# reflex_brainboard_RevG.net
KiCad netlist of a schematic drawn in Altium Designer
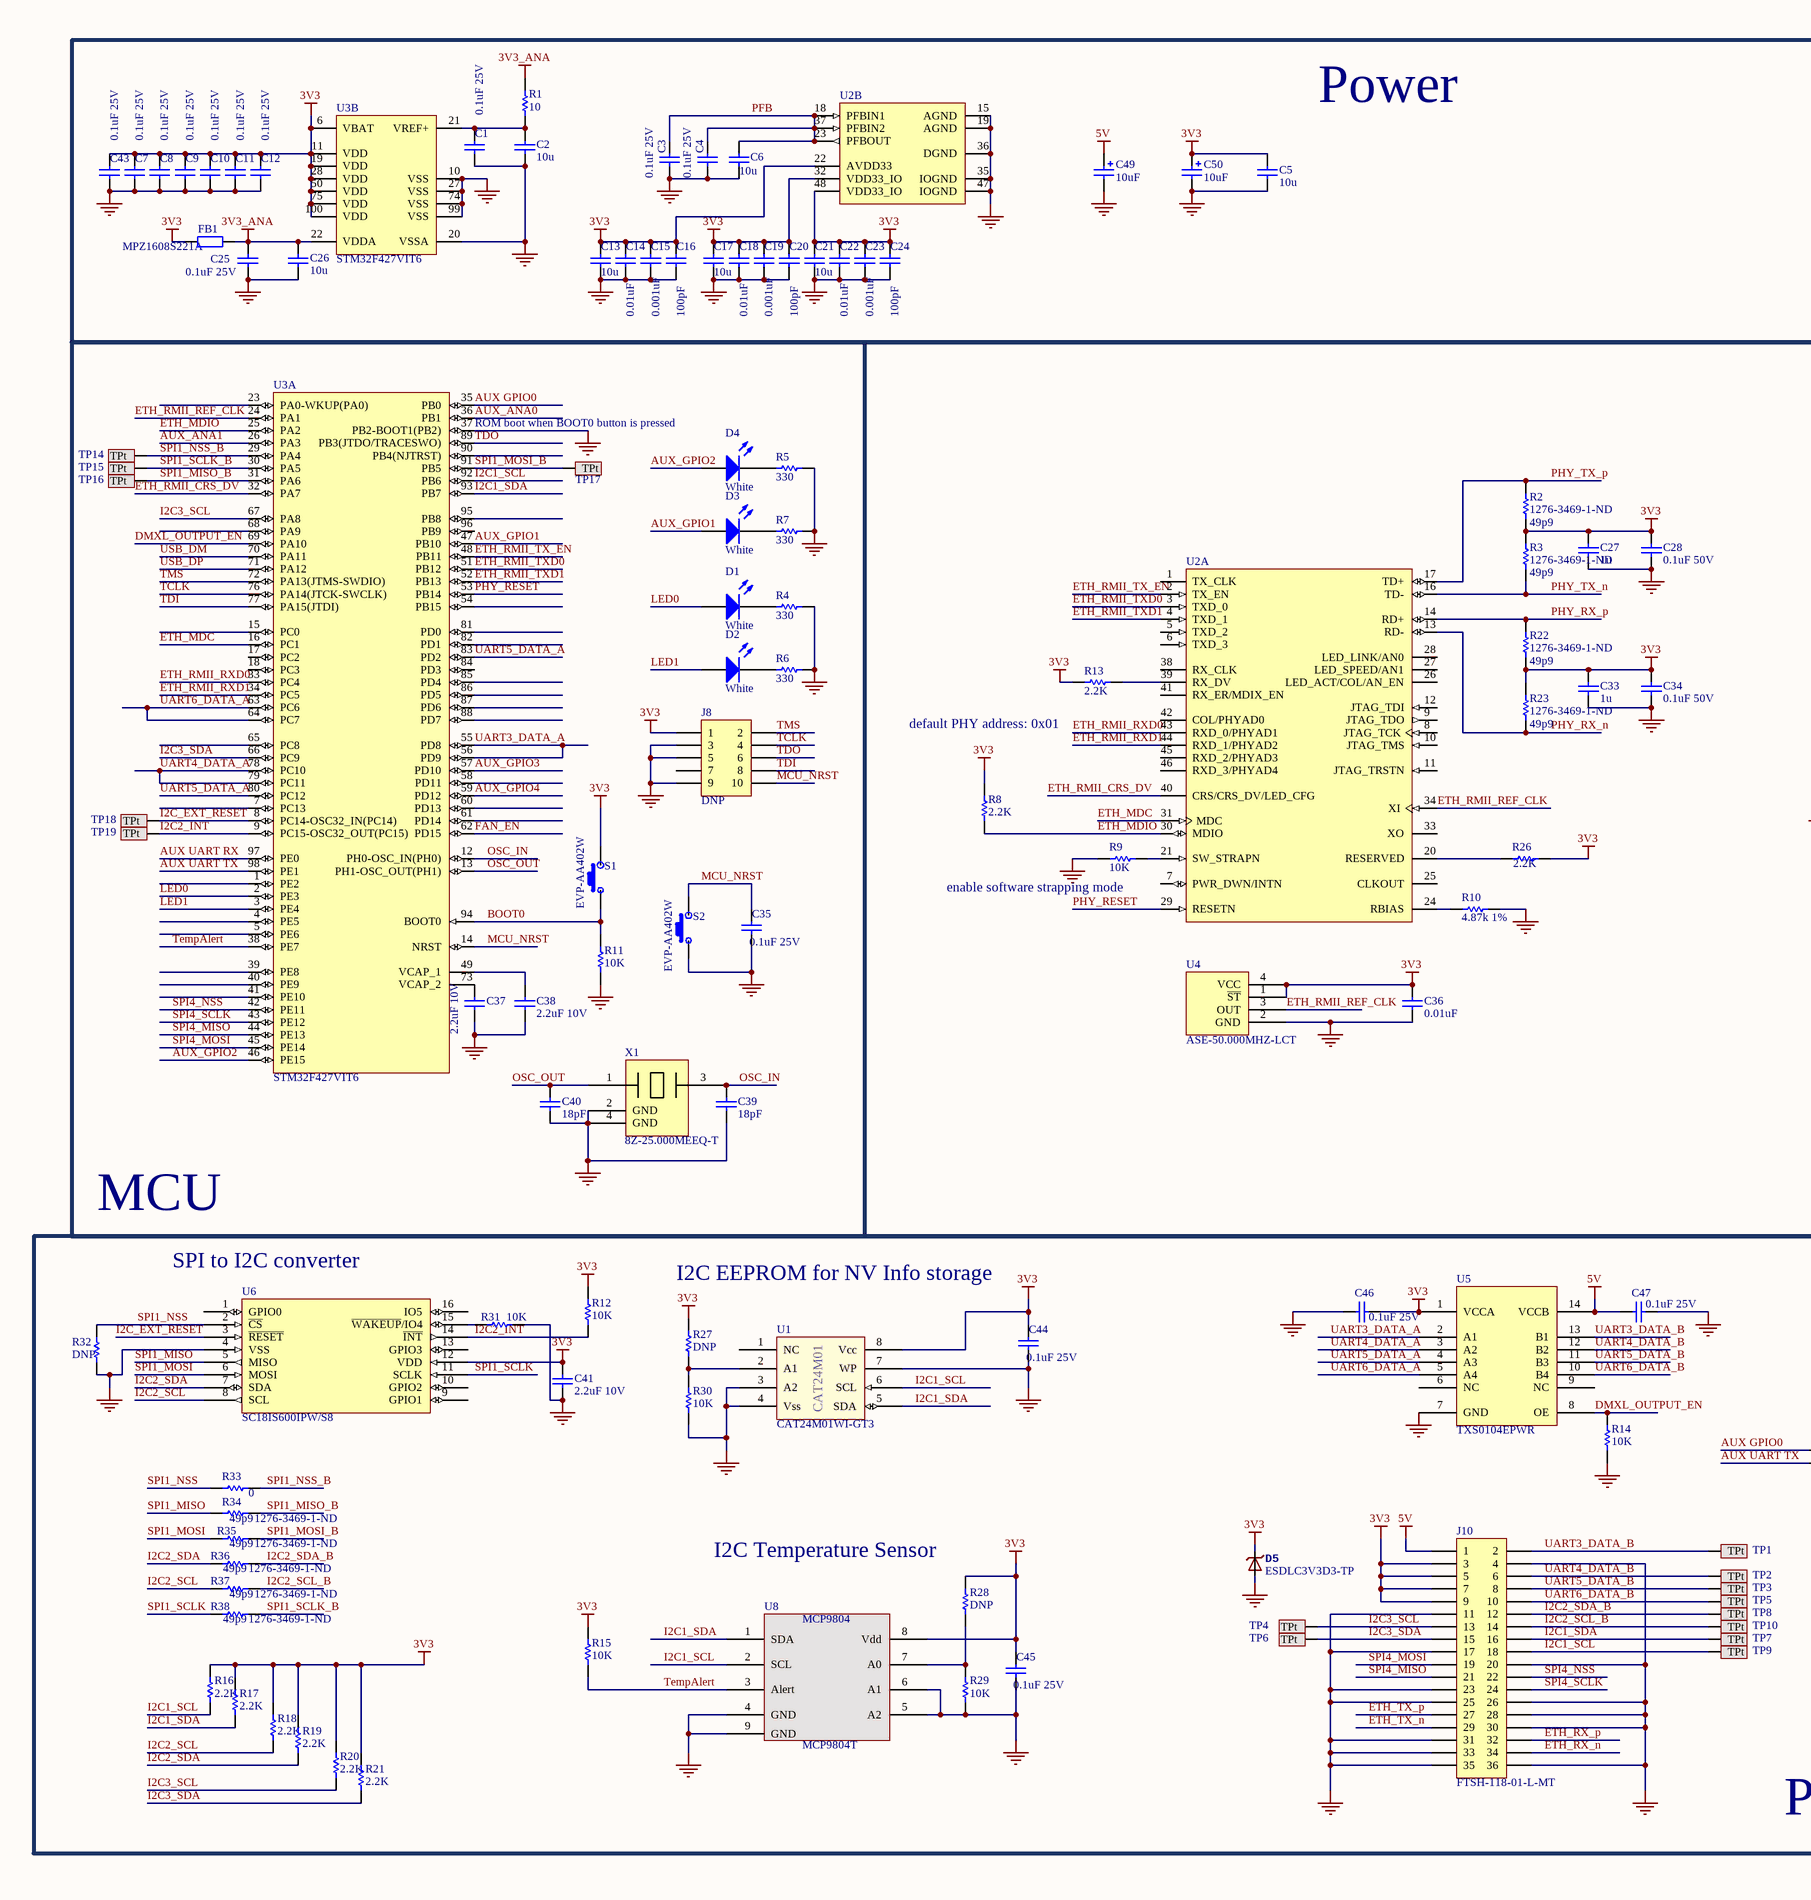
[diagram p0: reflex_brainboard_RevG.SchDoc, left]
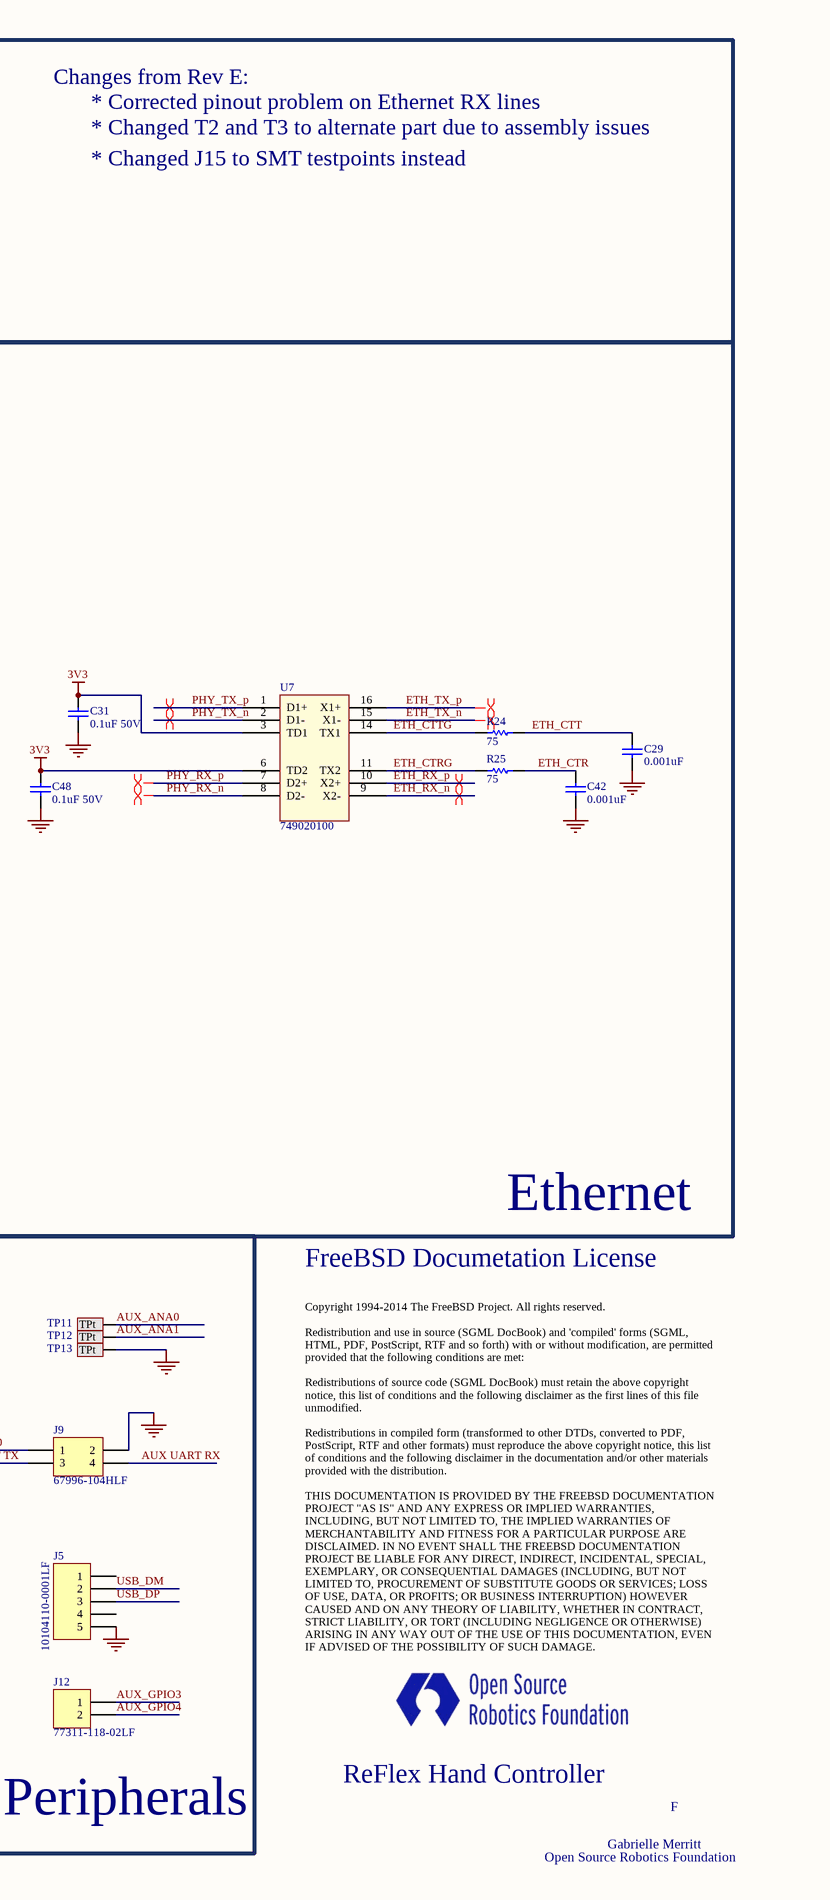
[diagram p1: reflex_brainboard_RevG.SchDoc, right]

(export (version "E")
  (design (tool "Eeschema 10.0.6"))
  (components
    (comp (ref "C1")
      (value "0.1uF 25V")
      (footprint "Generic_0603")
      (description "Capacitor 0.1uF 0603 package")
      (libsource (lib "RHR") (part "Cap_0603_0.1uF_25V"))
    )
    (comp (ref "C2")
      (value "10u")
      (footprint "GENERIC_0603")
      (description "Capacitor")
      (fields
        (field (name "MANUFACTURER") "TDK Corporation")
        (field (name "MANUFACTURER PART NUMBER") "C1608X5R1E106M080AC")
      )
      (libsource (lib "RHR") (part "Cap_0603_10uF"))
    )
    (comp (ref "C3")
      (value "0.1uF 25V")
      (footprint "Generic_0603")
      (description "Capacitor 0.1uF 0603 package")
      (libsource (lib "RHR") (part "Cap_0603_0.1uF_25V"))
    )
    (comp (ref "C4")
      (value "0.1uF 25V")
      (footprint "Generic_0603")
      (description "Capacitor 0.1uF 0603 package")
      (libsource (lib "RHR") (part "Cap_0603_0.1uF_25V"))
    )
    (comp (ref "C5")
      (value "10u")
      (footprint "GENERIC_0603")
      (description "Capacitor")
      (fields
        (field (name "MANUFACTURER") "TDK Corporation")
        (field (name "MANUFACTURER PART NUMBER") "C1608X5R1E106M080AC")
      )
      (libsource (lib "RHR") (part "Cap_0603_10uF"))
    )
    (comp (ref "C6")
      (value "10u")
      (footprint "GENERIC_0603")
      (description "Capacitor")
      (fields
        (field (name "MANUFACTURER") "TDK Corporation")
        (field (name "MANUFACTURER PART NUMBER") "C1608X5R1E106M080AC")
      )
      (libsource (lib "RHR") (part "Cap_0603_10uF"))
    )
    (comp (ref "C7")
      (value "0.1uF 25V")
      (footprint "Generic_0603")
      (description "Capacitor 0.1uF 0603 package")
      (libsource (lib "RHR") (part "Cap_0603_0.1uF_25V"))
    )
    (comp (ref "C8")
      (value "0.1uF 25V")
      (footprint "Generic_0603")
      (description "Capacitor 0.1uF 0603 package")
      (libsource (lib "RHR") (part "Cap_0603_0.1uF_25V"))
    )
    (comp (ref "C9")
      (value "0.1uF 25V")
      (footprint "Generic_0603")
      (description "Capacitor 0.1uF 0603 package")
      (libsource (lib "RHR") (part "Cap_0603_0.1uF_25V"))
    )
    (comp (ref "C10")
      (value "0.1uF 25V")
      (footprint "Generic_0603")
      (description "Capacitor 0.1uF 0603 package")
      (libsource (lib "RHR") (part "Cap_0603_0.1uF_25V"))
    )
    (comp (ref "C11")
      (value "0.1uF 25V")
      (footprint "Generic_0603")
      (description "Capacitor 0.1uF 0603 package")
      (libsource (lib "RHR") (part "Cap_0603_0.1uF_25V"))
    )
    (comp (ref "C12")
      (value "0.1uF 25V")
      (footprint "Generic_0603")
      (description "Capacitor 0.1uF 0603 package")
      (libsource (lib "RHR") (part "Cap_0603_0.1uF_25V"))
    )
    (comp (ref "C13")
      (value "10u")
      (footprint "GENERIC_0603")
      (description "Capacitor")
      (fields
        (field (name "MANUFACTURER") "TDK Corporation")
        (field (name "MANUFACTURER PART NUMBER") "C1608X5R1E106M080AC")
      )
      (libsource (lib "RHR") (part "Cap_0603_10uF"))
    )
    (comp (ref "C14")
      (value "0.01uF")
      (footprint "Generic_0402")
      (description "Capacitor 0.01uF 0402 package")
      (libsource (lib "RHR") (part "Cap_0402_0p01uF"))
    )
    (comp (ref "C15")
      (value "0.001uF")
      (footprint "Generic_0402")
      (description "Capacitor 0.001uF 0402 package")
      (libsource (lib "RHR") (part "Cap_0402_0p001uF"))
    )
    (comp (ref "C16")
      (value "100pF")
      (footprint "Generic_0402")
      (description "Capacitor 100pF 0402 package")
      (libsource (lib "RHR") (part "Cap_0402_100pF"))
    )
    (comp (ref "C17")
      (value "10u")
      (footprint "GENERIC_0603")
      (description "Capacitor")
      (fields
        (field (name "MANUFACTURER") "TDK Corporation")
        (field (name "MANUFACTURER PART NUMBER") "C1608X5R1E106M080AC")
      )
      (libsource (lib "RHR") (part "Cap_0603_10uF"))
    )
    (comp (ref "C18")
      (value "0.01uF")
      (footprint "Generic_0402")
      (description "Capacitor 0.01uF 0402 package")
      (libsource (lib "RHR") (part "Cap_0402_0p01uF"))
    )
    (comp (ref "C19")
      (value "0.001uF")
      (footprint "Generic_0402")
      (description "Capacitor 0.001uF 0402 package")
      (libsource (lib "RHR") (part "Cap_0402_0p001uF"))
    )
    (comp (ref "C20")
      (value "100pF")
      (footprint "Generic_0402")
      (description "Capacitor 100pF 0402 package")
      (libsource (lib "RHR") (part "Cap_0402_100pF"))
    )
    (comp (ref "C21")
      (value "10u")
      (footprint "GENERIC_0603")
      (description "Capacitor")
      (fields
        (field (name "MANUFACTURER") "TDK Corporation")
        (field (name "MANUFACTURER PART NUMBER") "C1608X5R1E106M080AC")
      )
      (libsource (lib "RHR") (part "Cap_0603_10uF"))
    )
    (comp (ref "C22")
      (value "0.01uF")
      (footprint "Generic_0402")
      (description "Capacitor 0.01uF 0402 package")
      (libsource (lib "RHR") (part "Cap_0402_0p01uF"))
    )
    (comp (ref "C23")
      (value "0.001uF")
      (footprint "Generic_0402")
      (description "Capacitor 0.001uF 0402 package")
      (libsource (lib "RHR") (part "Cap_0402_0p001uF"))
    )
    (comp (ref "C24")
      (value "100pF")
      (footprint "Generic_0402")
      (description "Capacitor 100pF 0402 package")
      (libsource (lib "RHR") (part "Cap_0402_100pF"))
    )
    (comp (ref "C25")
      (value "0.1uF 25V")
      (footprint "Generic_0603")
      (description "Capacitor 0.1uF 0603 package")
      (libsource (lib "RHR") (part "Cap_0603_0.1uF_25V"))
    )
    (comp (ref "C26")
      (value "10u")
      (footprint "GENERIC_0603")
      (description "Capacitor")
      (fields
        (field (name "MANUFACTURER") "TDK Corporation")
        (field (name "MANUFACTURER PART NUMBER") "C1608X5R1E106M080AC")
      )
      (libsource (lib "RHR") (part "Cap_0603_10uF"))
    )
    (comp (ref "C27")
      (value "1u")
      (footprint "Generic_0402")
      (description "Capacitor")
      (libsource (lib "RHR") (part "Cap_0402_1uF"))
    )
    (comp (ref "C28")
      (value "0.1uF 50V")
      (footprint "Generic_0402")
      (description "Capacitor 0.1uF 0402 package")
      (fields (field (name "Comment") "0.1uF"))
      (libsource (lib "RHR") (part "Cap_0402_0p1uF_50V"))
    )
    (comp (ref "C29")
      (value "0.001uF")
      (footprint "Generic_0402")
      (description "Capacitor 0.001uF 0402 package")
      (libsource (lib "RHR") (part "Cap_0402_0p001uF"))
    )
    (comp (ref "C31")
      (value "0.1uF 50V")
      (footprint "Generic_0402")
      (description "Capacitor 0.1uF 0402 package")
      (fields (field (name "Comment") "0.1uF"))
      (libsource (lib "RHR") (part "Cap_0402_0p1uF_50V"))
    )
    (comp (ref "C33")
      (value "1u")
      (footprint "Generic_0402")
      (description "Capacitor")
      (libsource (lib "RHR") (part "Cap_0402_1uF"))
    )
    (comp (ref "C34")
      (value "0.1uF 50V")
      (footprint "Generic_0402")
      (description "Capacitor 0.1uF 0402 package")
      (fields (field (name "Comment") "0.1uF"))
      (libsource (lib "RHR") (part "Cap_0402_0p1uF_50V"))
    )
    (comp (ref "C35")
      (value "0.1uF 25V")
      (footprint "Generic_0603")
      (description "Capacitor 0.1uF 0603 package")
      (libsource (lib "RHR") (part "Cap_0603_0.1uF_25V"))
    )
    (comp (ref "C36")
      (value "0.01uF")
      (footprint "Generic_0402")
      (description "Capacitor 0.01uF 0402 package")
      (libsource (lib "RHR") (part "Cap_0402_0p01uF"))
    )
    (comp (ref "C37")
      (value "2.2uF 10V")
      (footprint "Generic_0603")
      (description "Capacitor 2.2uF 0603 package")
      (libsource (lib "RHR") (part "Cap_0603_2p2uF_10V"))
    )
    (comp (ref "C38")
      (value "2.2uF 10V")
      (footprint "Generic_0603")
      (description "Capacitor 2.2uF 0603 package")
      (libsource (lib "RHR") (part "Cap_0603_2p2uF_10V"))
    )
    (comp (ref "C39")
      (value "18pF")
      (footprint "Generic_0402")
      (description "Capacitor 18pF 0402 package")
      (libsource (lib "RHR") (part "Cap_0402_18pF"))
    )
    (comp (ref "C40")
      (value "18pF")
      (footprint "Generic_0402")
      (description "Capacitor 18pF 0402 package")
      (libsource (lib "RHR") (part "Cap_0402_18pF"))
    )
    (comp (ref "C41")
      (value "2.2uF 10V")
      (footprint "Generic_0603")
      (description "Capacitor 2.2uF 0603 package")
      (libsource (lib "RHR") (part "Cap_0603_2p2uF_10V"))
    )
    (comp (ref "C42")
      (value "0.001uF")
      (footprint "Generic_0402")
      (description "Capacitor 0.001uF 0402 package")
      (libsource (lib "RHR") (part "Cap_0402_0p001uF"))
    )
    (comp (ref "C43")
      (value "0.1uF 25V")
      (footprint "Generic_0603")
      (description "Capacitor 0.1uF 0603 package")
      (libsource (lib "RHR") (part "Cap_0603_0.1uF_25V"))
    )
    (comp (ref "C44")
      (value "0.1uF 25V")
      (footprint "Generic_0603")
      (description "Capacitor 0.1uF 0603 package")
      (libsource (lib "RHR") (part "Cap_0603_0.1uF_25V"))
    )
    (comp (ref "C45")
      (value "0.1uF 25V")
      (footprint "Generic_0603")
      (description "Capacitor 0.1uF 0603 package")
      (libsource (lib "RHR") (part "Cap_0603_0.1uF_25V"))
    )
    (comp (ref "C46")
      (value "0.1uF 25V")
      (footprint "Generic_0603")
      (description "Capacitor 0.1uF 0603 package")
      (libsource (lib "RHR") (part "Cap_0603_0.1uF_25V"))
    )
    (comp (ref "C47")
      (value "0.1uF 25V")
      (footprint "Generic_0603")
      (description "Capacitor 0.1uF 0603 package")
      (libsource (lib "RHR") (part "Cap_0603_0.1uF_25V"))
    )
    (comp (ref "C48")
      (value "0.1uF 50V")
      (footprint "Generic_0402")
      (description "Capacitor 0.1uF 0402 package")
      (fields (field (name "Comment") "0.1uF"))
      (libsource (lib "RHR") (part "Cap_0402_0p1uF_50V"))
    )
    (comp (ref "C49")
      (value "10uF")
      (footprint "GENERIC_0805P")
      (description "Polarized Capacitor (Radial)")
      (libsource (lib "RHR") (part "Cap 0805P_10uF"))
    )
    (comp (ref "C50")
      (value "10uF")
      (footprint "GENERIC_0805P")
      (description "Polarized Capacitor (Radial)")
      (libsource (lib "RHR") (part "Cap 0805P_10uF"))
    )
    (comp (ref "D1")
      (value "White")
      (footprint "0402_LED_WHITE")
      (description "Surface mount LEDs")
      (fields (field (name "Comment") "LED White"))
      (libsource (lib "RHR") (part "LED_White_0402"))
    )
    (comp (ref "D2")
      (value "White")
      (footprint "0402_LED_WHITE")
      (description "Surface mount LEDs")
      (fields (field (name "Comment") "LED White"))
      (libsource (lib "RHR") (part "LED_White_0402"))
    )
    (comp (ref "D3")
      (value "White")
      (footprint "0402_LED_WHITE")
      (description "Surface mount LEDs")
      (fields (field (name "Comment") "LED White"))
      (libsource (lib "RHR") (part "LED_White_0402"))
    )
    (comp (ref "D4")
      (value "White")
      (footprint "0402_LED_WHITE")
      (description "Surface mount LEDs")
      (fields (field (name "Comment") "LED White"))
      (libsource (lib "RHR") (part "LED_White_0402"))
    )
    (comp (ref "D5")
      (value "ESDLC3V3D3-TP")
      (footprint "SOD-323")
      (fields (field (name "MANUFACTURER") "Micro Commercial Co"))
      (libsource (lib "RHR") (part "Diode_ESDLC3V3D3-TP"))
    )
    (comp (ref "FB1")
      (value "MPZ1608S221A")
      (footprint "GENERIC_0603")
      (description "Ferrite Bead")
      (fields (field (name "MANUFACTURER") "TDK Corporation"))
      (libsource (lib "RHR") (part "FerriteBead"))
    )
    (comp (ref "J5")
      (value "10104110-0001LF")
      (footprint "FCI-10104110")
      (description "USB Micro Connector")
      (libsource (lib "RHR") (part "Conn_USB_Micro"))
    )
    (comp (ref "J8")
      (value "DNP")
      (footprint "CNCTECH_3220-10-0300-00")
      (description "Header, 5-Pin, Dual row")
      (libsource (lib "RHR") (part "Header 5X2"))
    )
    (comp (ref "J9")
      (value "67996-104HLF")
      (footprint "HDR2X2")
      (description "Header, 2-Pin, Dual row")
      (libsource (lib "RHR") (part "Header 2X2"))
    )
    (comp (ref "J10")
      (value "FTSH-118-01-L-MT")
      (footprint "FTSH-118-01-L-MT")
      (description "Header, 18-Pin, Dual row, Hybrid SMT/Thru")
      (libsource (lib "RHR") (part "Header 18X2 RA MT"))
    )
    (comp (ref "J12")
      (value "77311-118-02LF")
      (footprint "HDR1X2")
      (description "Header, 2-Pin")
      (libsource (lib "RHR") (part "Header 2"))
    )
    (comp (ref "R1")
      (value "10")
      (footprint "Generic_0402")
      (description "Resistor  10 ohm")
      (libsource (lib "RHR") (part "Res_0402_10_1pct"))
    )
    (comp (ref "R2")
      (value "49p9")
      (footprint "Generic_0402")
      (description "Resistor 49.9 ohm")
      (fields
        (field (name "SUPPLIER PART NUMBER 1") "1276-3469-1-ND")
        (field (name "Comment") "Res_0402_49p9_1pct")
      )
      (libsource (lib "RHR") (part "Res_0402_49p9_1pct"))
    )
    (comp (ref "R3")
      (value "49p9")
      (footprint "Generic_0402")
      (description "Resistor 49.9 ohm")
      (fields
        (field (name "SUPPLIER PART NUMBER 1") "1276-3469-1-ND")
        (field (name "Comment") "Res_0402_49p9_1pct")
      )
      (libsource (lib "RHR") (part "Res_0402_49p9_1pct"))
    )
    (comp (ref "R4")
      (value "330")
      (footprint "Generic_0402")
      (description "RES 330 OHM 1/10W 1% 0402 SMD")
      (libsource (lib "RHR") (part "Res_0402_330"))
    )
    (comp (ref "R5")
      (value "330")
      (footprint "Generic_0402")
      (description "RES 330 OHM 1/10W 1% 0402 SMD")
      (libsource (lib "RHR") (part "Res_0402_330"))
    )
    (comp (ref "R6")
      (value "330")
      (footprint "Generic_0402")
      (description "RES 330 OHM 1/10W 1% 0402 SMD")
      (libsource (lib "RHR") (part "Res_0402_330"))
    )
    (comp (ref "R7")
      (value "330")
      (footprint "Generic_0402")
      (description "RES 330 OHM 1/10W 1% 0402 SMD")
      (libsource (lib "RHR") (part "Res_0402_330"))
    )
    (comp (ref "R8")
      (value "2.2K")
      (footprint "Generic_0402")
      (description "Resistor 2.2 Kohm")
      (fields (field (name "Comment") "Res_0402_2.2K"))
      (libsource (lib "RHR") (part "Res_0402_2.2K"))
    )
    (comp (ref "R9")
      (value "10K")
      (footprint "Generic_0402")
      (description "Resistor 10 Kohm")
      (fields (field (name "Comment") "Res_0402_10K_1pct"))
      (libsource (lib "RHR") (part "Res_0402_10K_1pct"))
    )
    (comp (ref "R10")
      (value "4.87k 1%")
      (footprint "Generic_0402")
      (description "75R 0.063W 5% 0402 (1005 Metric)  SMD")
      (libsource (lib "RHR") (part "Res_0402_4p87K_1pct"))
    )
    (comp (ref "R11")
      (value "10K")
      (footprint "Generic_0402")
      (description "Resistor 10 Kohm")
      (fields (field (name "Comment") "Res_0402_10K_1pct"))
      (libsource (lib "RHR") (part "Res_0402_10K_1pct"))
    )
    (comp (ref "R12")
      (value "10K")
      (footprint "Generic_0402")
      (description "Resistor 10 Kohm")
      (fields (field (name "Comment") "Res_0402_10K_1pct"))
      (libsource (lib "RHR") (part "Res_0402_10K_1pct"))
    )
    (comp (ref "R13")
      (value "2.2K")
      (footprint "Generic_0402")
      (description "Resistor 2.2 Kohm")
      (fields (field (name "Comment") "Res_0402_2.2K"))
      (libsource (lib "RHR") (part "Res_0402_2.2K"))
    )
    (comp (ref "R14")
      (value "10K")
      (footprint "Generic_0402")
      (description "Resistor 10 Kohm")
      (fields (field (name "Comment") "Res_0402_10K_1pct"))
      (libsource (lib "RHR") (part "Res_0402_10K_1pct"))
    )
    (comp (ref "R15")
      (value "10K")
      (footprint "Generic_0402")
      (description "Resistor 10 Kohm")
      (fields (field (name "Comment") "Res_0402_10K_1pct"))
      (libsource (lib "RHR") (part "Res_0402_10K_1pct"))
    )
    (comp (ref "R16")
      (value "2.2K")
      (footprint "Generic_0402")
      (description "Resistor 2.2 Kohm")
      (fields (field (name "Comment") "Res_0402_2.2K"))
      (libsource (lib "RHR") (part "Res_0402_2.2K"))
    )
    (comp (ref "R17")
      (value "2.2K")
      (footprint "Generic_0402")
      (description "Resistor 2.2 Kohm")
      (fields (field (name "Comment") "Res_0402_2.2K"))
      (libsource (lib "RHR") (part "Res_0402_2.2K"))
    )
    (comp (ref "R18")
      (value "2.2K")
      (footprint "Generic_0402")
      (description "Resistor 2.2 Kohm")
      (fields (field (name "Comment") "Res_0402_2.2K"))
      (libsource (lib "RHR") (part "Res_0402_2.2K"))
    )
    (comp (ref "R19")
      (value "2.2K")
      (footprint "Generic_0402")
      (description "Resistor 2.2 Kohm")
      (fields (field (name "Comment") "Res_0402_2.2K"))
      (libsource (lib "RHR") (part "Res_0402_2.2K"))
    )
    (comp (ref "R20")
      (value "2.2K")
      (footprint "Generic_0402")
      (description "Resistor 2.2 Kohm")
      (fields (field (name "Comment") "Res_0402_2.2K"))
      (libsource (lib "RHR") (part "Res_0402_2.2K"))
    )
    (comp (ref "R21")
      (value "2.2K")
      (footprint "Generic_0402")
      (description "Resistor 2.2 Kohm")
      (fields (field (name "Comment") "Res_0402_2.2K"))
      (libsource (lib "RHR") (part "Res_0402_2.2K"))
    )
    (comp (ref "R22")
      (value "49p9")
      (footprint "Generic_0402")
      (description "Resistor 49.9 ohm")
      (fields
        (field (name "SUPPLIER PART NUMBER 1") "1276-3469-1-ND")
        (field (name "Comment") "Res_0402_49p9_1pct")
      )
      (libsource (lib "RHR") (part "Res_0402_49p9_1pct"))
    )
    (comp (ref "R23")
      (value "49p9")
      (footprint "Generic_0402")
      (description "Resistor 49.9 ohm")
      (fields
        (field (name "SUPPLIER PART NUMBER 1") "1276-3469-1-ND")
        (field (name "Comment") "Res_0402_49p9_1pct")
      )
      (libsource (lib "RHR") (part "Res_0402_49p9_1pct"))
    )
    (comp (ref "R24")
      (value "75")
      (footprint "Generic_0402")
      (description "75R 0.063W 5% 0402 (1005 Metric)  SMD")
      (libsource (lib "RHR") (part "Res_0402_75_1pct"))
    )
    (comp (ref "R25")
      (value "75")
      (footprint "Generic_0402")
      (description "75R 0.063W 5% 0402 (1005 Metric)  SMD")
      (libsource (lib "RHR") (part "Res_0402_75_1pct"))
    )
    (comp (ref "R26")
      (value "2.2K")
      (footprint "Generic_0402")
      (description "Resistor 2.2 Kohm")
      (fields (field (name "Comment") "Res_0402_2.2K"))
      (libsource (lib "RHR") (part "Res_0402_2.2K"))
    )
    (comp (ref "R27")
      (value "DNP")
      (footprint "Generic_0402")
      (description "Resistor 0402 DNP")
      (fields (field (name "Comment") "Res_0402_DNP"))
      (libsource (lib "RHR") (part "Res_0402_DNP"))
    )
    (comp (ref "R28")
      (value "DNP")
      (footprint "Generic_0402")
      (description "Resistor 0402 DNP")
      (fields (field (name "Comment") "Res_0402_DNP"))
      (libsource (lib "RHR") (part "Res_0402_DNP"))
    )
    (comp (ref "R29")
      (value "10K")
      (footprint "Generic_0402")
      (description "Resistor 10 Kohm")
      (fields (field (name "Comment") "Res_0402_10K_1pct"))
      (libsource (lib "RHR") (part "Res_0402_10K_1pct"))
    )
    (comp (ref "R30")
      (value "10K")
      (footprint "Generic_0402")
      (description "Resistor 10 Kohm")
      (fields (field (name "Comment") "Res_0402_10K_1pct"))
      (libsource (lib "RHR") (part "Res_0402_10K_1pct"))
    )
    (comp (ref "R31")
      (value "10K")
      (footprint "Generic_0402")
      (description "Resistor 10 Kohm")
      (fields (field (name "Comment") "Res_0402_10K_1pct"))
      (libsource (lib "RHR") (part "Res_0402_10K_1pct"))
    )
    (comp (ref "R32")
      (value "DNP")
      (footprint "Generic_0402")
      (description "Resistor 0402 DNP")
      (fields (field (name "Comment") "Res_0402_DNP"))
      (libsource (lib "RHR") (part "Res_0402_DNP"))
    )
    (comp (ref "R33")
      (value "0")
      (footprint "GENERIC_0402")
      (description "RES SMD 0 OHM JUMPER 1/10W 0402")
      (fields (field (name "Comment") "Res_0402_0"))
      (libsource (lib "RHR") (part "Res_0402_0"))
    )
    (comp (ref "R34")
      (value "49p9")
      (footprint "Generic_0402")
      (description "Resistor 49.9 ohm")
      (fields
        (field (name "SUPPLIER PART NUMBER 1") "1276-3469-1-ND")
        (field (name "Comment") "Res_0402_49p9_1pct")
      )
      (libsource (lib "RHR") (part "Res_0402_49p9_1pct"))
    )
    (comp (ref "R35")
      (value "49p9")
      (footprint "Generic_0402")
      (description "Resistor 49.9 ohm")
      (fields
        (field (name "SUPPLIER PART NUMBER 1") "1276-3469-1-ND")
        (field (name "Comment") "Res_0402_49p9_1pct")
      )
      (libsource (lib "RHR") (part "Res_0402_49p9_1pct"))
    )
    (comp (ref "R36")
      (value "49p9")
      (footprint "Generic_0402")
      (description "Resistor 49.9 ohm")
      (fields
        (field (name "SUPPLIER PART NUMBER 1") "1276-3469-1-ND")
        (field (name "Comment") "Res_0402_49p9_1pct")
      )
      (libsource (lib "RHR") (part "Res_0402_49p9_1pct"))
    )
    (comp (ref "R37")
      (value "49p9")
      (footprint "Generic_0402")
      (description "Resistor 49.9 ohm")
      (fields
        (field (name "SUPPLIER PART NUMBER 1") "1276-3469-1-ND")
        (field (name "Comment") "Res_0402_49p9_1pct")
      )
      (libsource (lib "RHR") (part "Res_0402_49p9_1pct"))
    )
    (comp (ref "R38")
      (value "49p9")
      (footprint "Generic_0402")
      (description "Resistor 49.9 ohm")
      (fields
        (field (name "SUPPLIER PART NUMBER 1") "1276-3469-1-ND")
        (field (name "Comment") "Res_0402_49p9_1pct")
      )
      (libsource (lib "RHR") (part "Res_0402_49p9_1pct"))
    )
    (comp (ref "S1")
      (value "EVP-AA402W")
      (footprint "EVPAA402_switch")
      (description "Momentary Push button, NO")
      (libsource (lib "RHR") (part "Pushbutton_EVP-AA402W"))
    )
    (comp (ref "S2")
      (value "EVP-AA402W")
      (footprint "EVPAA402_switch")
      (description "Momentary Push button, NO")
      (libsource (lib "RHR") (part "Pushbutton_EVP-AA402W"))
    )
    (comp (ref "TP1")
      (value "SMT Pad")
      (footprint "TP_PAD_20mil")
      (description "SMT pad for test")
      (libsource (lib "RHR") (part "TP_SMT_20mil"))
    )
    (comp (ref "TP2")
      (value "SMT Pad")
      (footprint "TP_PAD_20mil")
      (description "SMT pad for test")
      (libsource (lib "RHR") (part "TP_SMT_20mil"))
    )
    (comp (ref "TP3")
      (value "SMT Pad")
      (footprint "TP_PAD_20mil")
      (description "SMT pad for test")
      (libsource (lib "RHR") (part "TP_SMT_20mil"))
    )
    (comp (ref "TP4")
      (value "SMT Pad")
      (footprint "TP_PAD_20mil")
      (description "SMT pad for test")
      (libsource (lib "") (part "TP_SMT_20mil_1"))
    )
    (comp (ref "TP5")
      (value "SMT Pad")
      (footprint "TP_PAD_20mil")
      (description "SMT pad for test")
      (libsource (lib "RHR") (part "TP_SMT_20mil"))
    )
    (comp (ref "TP6")
      (value "SMT Pad")
      (footprint "TP_PAD_20mil")
      (description "SMT pad for test")
      (libsource (lib "") (part "TP_SMT_20mil_1"))
    )
    (comp (ref "TP7")
      (value "SMT Pad")
      (footprint "TP_PAD_20mil")
      (description "SMT pad for test")
      (libsource (lib "RHR") (part "TP_SMT_20mil"))
    )
    (comp (ref "TP8")
      (value "SMT Pad")
      (footprint "TP_PAD_20mil")
      (description "SMT pad for test")
      (libsource (lib "RHR") (part "TP_SMT_20mil"))
    )
    (comp (ref "TP9")
      (value "SMT Pad")
      (footprint "TP_PAD_20mil")
      (description "SMT pad for test")
      (libsource (lib "RHR") (part "TP_SMT_20mil"))
    )
    (comp (ref "TP10")
      (value "SMT Pad")
      (footprint "TP_PAD_20mil")
      (description "SMT pad for test")
      (libsource (lib "RHR") (part "TP_SMT_20mil"))
    )
    (comp (ref "TP11")
      (value "SMT Pad")
      (footprint "TP_PAD_20mil")
      (description "SMT pad for test")
      (libsource (lib "") (part "TP_SMT_20mil_1"))
    )
    (comp (ref "TP12")
      (value "SMT Pad")
      (footprint "TP_PAD_20mil")
      (description "SMT pad for test")
      (libsource (lib "") (part "TP_SMT_20mil_1"))
    )
    (comp (ref "TP13")
      (value "SMT Pad")
      (footprint "TP_PAD_20mil")
      (description "SMT pad for test")
      (libsource (lib "") (part "TP_SMT_20mil_1"))
    )
    (comp (ref "TP14")
      (value "SMT Pad")
      (footprint "TP_PAD_20mil")
      (description "SMT pad for test")
      (libsource (lib "") (part "TP_SMT_20mil_1"))
    )
    (comp (ref "TP15")
      (value "SMT Pad")
      (footprint "TP_PAD_20mil")
      (description "SMT pad for test")
      (libsource (lib "") (part "TP_SMT_20mil_1"))
    )
    (comp (ref "TP16")
      (value "SMT Pad")
      (footprint "TP_PAD_20mil")
      (description "SMT pad for test")
      (libsource (lib "") (part "TP_SMT_20mil_1"))
    )
    (comp (ref "TP17")
      (value "SMT Pad")
      (footprint "TP_PAD_20mil")
      (description "SMT pad for test")
      (libsource (lib "RHR") (part "TP_SMT_20mil"))
    )
    (comp (ref "TP18")
      (value "SMT Pad")
      (footprint "TP_PAD_20mil")
      (description "SMT pad for test")
      (libsource (lib "") (part "TP_SMT_20mil_1"))
    )
    (comp (ref "TP19")
      (value "SMT Pad")
      (footprint "TP_PAD_20mil")
      (description "SMT pad for test")
      (libsource (lib "") (part "TP_SMT_20mil_1"))
    )
    (comp (ref "U1")
      (value "CAT24M01WI-GT3")
      (footprint "SOIC8")
      (description "I2C EEPROM 1Mbit")
      (libsource (lib "RHR") (part "IC_EEPROM_I2C_1Mbit"))
    )
    (comp (ref "U2")
      (value "TLK110PT")
      (footprint "PT0048A_M")
      (libsource (lib "Altium Content Vault") (part "TI-TLK110-LQFP_PT-48"))
    )
    (comp (ref "U3")
      (value "STM32F427VIT6")
      (footprint "STM-LQFP100_N")
      (fields (field (name "MANUFACTURER") "STMicroelectronics"))
      (libsource (lib "RHR") (part "MC-ARM-STM32F4X7-SQ100"))
    )
    (comp (ref "U4")
      (value "ASE-50.000MHZ-LCT")
      (footprint "OSCILLATOR_3.2x2.5")
      (libsource (lib "RHR") (part "oscillator_3.2x2.5"))
    )
    (comp (ref "U5")
      (value "TXS0104EPWR")
      (footprint "TXS0104EPWR")
      (description "Level Shifter")
      (libsource (lib "RHR") (part "IC_LevelShifter_TXS0104EPWR"))
    )
    (comp (ref "U6")
      (value "SC18IS600IPW/S8")
      (footprint "SOT403-1-TSSOP16")
      (description "SPI to I2C-bus interface")
      (libsource (lib "Schlib1") (part "SC18IS600IPW/S8"))
    )
    (comp (ref "U7")
      (value "749020100")
      (footprint "Wurth749020100")
      (description "Ethernet Magnetics Wurth 749020100")
      (libsource (lib "RHR") (part "IC_EthernetMagnetics"))
    )
    (comp (ref "U8")
      (value "MCP9804T")
      (footprint "Temp_MCP9804T")
      (description "I2C Temp Sensor MCP9804T-E/MC")
      (libsource (lib "RHR") (part "IC_Temp_Sensor_MCP9804_I2C"))
    )
    (comp (ref "X1")
      (value "8Z-25.000MEEQ-T")
      (footprint "CRYSTAL_2_2.5")
      (libsource (lib "RHR") (part "CRYSTAL"))
    )
  )
  (nets
    (net (code "1") (name "/AUX GPIO0") (class "Default")
      (node (ref "J9") (pin "1") (pinfunction "1_1") (pintype "passive"))
      (node (ref "U3") (pin "35") (pinfunction "PB0_35") (pintype "bidirectional"))
    )
    (net (code "2") (name "/AUX UART RX") (class "Default")
      (node (ref "J9") (pin "4") (pinfunction "4_4") (pintype "passive"))
      (node (ref "U3") (pin "97") (pinfunction "PE0_97") (pintype "bidirectional"))
    )
    (net (code "3") (name "/AUX UART TX") (class "Default")
      (node (ref "J9") (pin "3") (pinfunction "3_3") (pintype "passive"))
      (node (ref "U3") (pin "98") (pinfunction "PE1_98") (pintype "bidirectional"))
    )
    (net (code "4") (name "/AUX_ANA0") (class "Default")
      (node (ref "TP11") (pin "1") (pinfunction "TPt_1") (pintype "passive"))
      (node (ref "U3") (pin "36") (pinfunction "PB1_36") (pintype "bidirectional"))
    )
    (net (code "5") (name "/AUX_ANA1") (class "Default")
      (node (ref "TP12") (pin "1") (pinfunction "TPt_1") (pintype "passive"))
      (node (ref "U3") (pin "26") (pinfunction "PA3_26") (pintype "bidirectional"))
    )
    (net (code "6") (name "/AUX_GPIO1") (class "Default")
      (node (ref "D3") (pin "1") (pinfunction "A_1") (pintype "passive"))
      (node (ref "U3") (pin "47") (pinfunction "PB10_47") (pintype "bidirectional"))
    )
    (net (code "7") (name "/AUX_GPIO2") (class "Default")
      (node (ref "D4") (pin "1") (pinfunction "A_1") (pintype "passive"))
      (node (ref "U3") (pin "46") (pinfunction "PE15_46") (pintype "bidirectional"))
    )
    (net (code "8") (name "/AUX_GPIO3") (class "Default")
      (node (ref "J12") (pin "1") (pinfunction "1_1") (pintype "passive"))
      (node (ref "U3") (pin "57") (pinfunction "PD10_57") (pintype "bidirectional"))
    )
    (net (code "9") (name "/AUX_GPIO4") (class "Default")
      (node (ref "J12") (pin "2") (pinfunction "2_2") (pintype "passive"))
      (node (ref "U3") (pin "59") (pinfunction "PD12_59") (pintype "bidirectional"))
    )
    (net (code "10") (name "/BOOT0") (class "Default")
      (node (ref "R11") (pin "2") (pinfunction "2_2") (pintype "passive"))
      (node (ref "S1") (pin "2") (pinfunction "2_2") (pintype "power_in"))
      (node (ref "U3") (pin "94") (pinfunction "BOOT0_94") (pintype "input"))
    )
    (net (code "11") (name "/DMXL_OUTPUT_EN") (class "Default")
      (node (ref "R14") (pin "2") (pinfunction "2_2") (pintype "passive"))
      (node (ref "U3") (pin "69") (pinfunction "PA10_69") (pintype "bidirectional"))
      (node (ref "U5") (pin "8") (pinfunction "OE_8") (pintype "power_in"))
    )
    (net (code "12") (name "/ETH_CTR") (class "Default")
      (node (ref "C42") (pin "2") (pinfunction "2_2") (pintype "passive"))
      (node (ref "R25") (pin "2") (pinfunction "2_2") (pintype "passive"))
    )
    (net (code "13") (name "/ETH_CTRG") (class "Default")
      (node (ref "R25") (pin "1") (pinfunction "1_1") (pintype "passive"))
      (node (ref "U7") (pin "11") (pinfunction "TX2_11") (pintype "passive"))
    )
    (net (code "14") (name "/ETH_CTT") (class "Default")
      (node (ref "C29") (pin "2") (pinfunction "2_2") (pintype "passive"))
      (node (ref "R24") (pin "2") (pinfunction "2_2") (pintype "passive"))
    )
    (net (code "15") (name "/ETH_CTTG") (class "Default")
      (node (ref "R24") (pin "1") (pinfunction "1_1") (pintype "passive"))
      (node (ref "U7") (pin "14") (pinfunction "TX1_14") (pintype "passive"))
    )
    (net (code "16") (name "/ETH_MDC") (class "Default")
      (node (ref "U2") (pin "31") (pinfunction "MDC_31") (pintype "input"))
      (node (ref "U3") (pin "16") (pinfunction "PC1_16") (pintype "bidirectional"))
    )
    (net (code "17") (name "/ETH_MDIO") (class "Default")
      (node (ref "R8") (pin "2") (pinfunction "2_2") (pintype "passive"))
      (node (ref "U2") (pin "30") (pinfunction "MDIO_30") (pintype "bidirectional"))
      (node (ref "U3") (pin "25") (pinfunction "PA2_25") (pintype "bidirectional"))
    )
    (net (code "18") (name "/ETH_RMII_CRS_DV") (class "Default")
      (node (ref "U2") (pin "40") (pinfunction "CRS/CRS_DV/LED_CFG_40") (pintype "tri_state"))
      (node (ref "U3") (pin "32") (pinfunction "PA7_32") (pintype "bidirectional"))
    )
    (net (code "19") (name "/ETH_RMII_REF_CLK") (class "Default")
      (node (ref "U2") (pin "34") (pinfunction "XI_34") (pintype "input"))
      (node (ref "U3") (pin "24") (pinfunction "PA1_24") (pintype "bidirectional"))
      (node (ref "U4") (pin "3") (pinfunction "OUT_3") (pintype "passive"))
    )
    (net (code "20") (name "/ETH_RMII_RXD0") (class "Default")
      (node (ref "U2") (pin "43") (pinfunction "RXD_0/PHYAD1_43") (pintype "tri_state"))
      (node (ref "U3") (pin "33") (pinfunction "PC4_33") (pintype "bidirectional"))
    )
    (net (code "21") (name "/ETH_RMII_RXD1") (class "Default")
      (node (ref "U2") (pin "44") (pinfunction "RXD_1/PHYAD2_44") (pintype "tri_state"))
      (node (ref "U3") (pin "34") (pinfunction "PC5_34") (pintype "bidirectional"))
    )
    (net (code "22") (name "/ETH_RMII_TXD0") (class "Default")
      (node (ref "U2") (pin "3") (pinfunction "TXD_0_3") (pintype "input"))
      (node (ref "U3") (pin "51") (pinfunction "PB12_51") (pintype "bidirectional"))
    )
    (net (code "23") (name "/ETH_RMII_TXD1") (class "Default")
      (node (ref "U2") (pin "4") (pinfunction "TXD_1_4") (pintype "input"))
      (node (ref "U3") (pin "52") (pinfunction "PB13_52") (pintype "bidirectional"))
    )
    (net (code "24") (name "/ETH_RMII_TX_EN") (class "Default")
      (node (ref "U2") (pin "2") (pinfunction "TX_EN_2") (pintype "input"))
      (node (ref "U3") (pin "48") (pinfunction "PB11_48") (pintype "bidirectional"))
    )
    (net (code "25") (name "/ETH_RX_n") (class "Default")
      (node (ref "J10") (pin "34") (pinfunction "34_34") (pintype "passive"))
      (node (ref "U7") (pin "9") (pinfunction "X2-_9") (pintype "passive"))
    )
    (net (code "26") (name "/ETH_RX_p") (class "Default")
      (node (ref "J10") (pin "32") (pinfunction "32_32") (pintype "passive"))
      (node (ref "U7") (pin "10") (pinfunction "X2+_10") (pintype "passive"))
    )
    (net (code "27") (name "/ETH_TX_n") (class "Default")
      (node (ref "J10") (pin "29") (pinfunction "29_29") (pintype "passive"))
      (node (ref "U7") (pin "15") (pinfunction "X1-_15") (pintype "passive"))
    )
    (net (code "28") (name "/ETH_TX_p") (class "Default")
      (node (ref "J10") (pin "27") (pinfunction "27_27") (pintype "passive"))
      (node (ref "U7") (pin "16") (pinfunction "X1+_16") (pintype "passive"))
    )
    (net (code "29") (name "/FAN_EN") (class "Default")
      (node (ref "U3") (pin "62") (pinfunction "PD15_62") (pintype "bidirectional"))
    )
    (net (code "30") (name "/I2C1_SCL") (class "Default")
      (node (ref "J10") (pin "18") (pinfunction "18_18") (pintype "passive"))
      (node (ref "R16") (pin "1") (pinfunction "1_1") (pintype "passive"))
      (node (ref "TP9") (pin "1") (pinfunction "TPt_1") (pintype "passive"))
      (node (ref "U1") (pin "6") (pinfunction "SCL_6") (pintype "input"))
      (node (ref "U3") (pin "92") (pinfunction "PB6_92") (pintype "bidirectional"))
      (node (ref "U8") (pin "2") (pinfunction "SCL_2") (pintype "passive"))
    )
    (net (code "31") (name "/I2C1_SDA") (class "Default")
      (node (ref "J10") (pin "16") (pinfunction "16_16") (pintype "passive"))
      (node (ref "R17") (pin "1") (pinfunction "1_1") (pintype "passive"))
      (node (ref "TP7") (pin "1") (pinfunction "TPt_1") (pintype "passive"))
      (node (ref "U1") (pin "5") (pinfunction "SDA_5") (pintype "bidirectional"))
      (node (ref "U3") (pin "93") (pinfunction "PB7_93") (pintype "bidirectional"))
      (node (ref "U8") (pin "1") (pinfunction "SDA_1") (pintype "passive"))
    )
    (net (code "32") (name "/I2C2_INT") (class "Default")
      (node (ref "R12") (pin "1") (pinfunction "1_1") (pintype "passive"))
      (node (ref "TP19") (pin "1") (pinfunction "TPt_1") (pintype "passive"))
      (node (ref "U3") (pin "9") (pinfunction "PC15-OSC32_OUT(PC15)_9") (pintype "bidirectional"))
      (node (ref "U6") (pin "14") (pinfunction "~{INT}_14") (pintype "output"))
    )
    (net (code "33") (name "/I2C2_SCL") (class "Default")
      (node (ref "R18") (pin "1") (pinfunction "1_1") (pintype "passive"))
      (node (ref "R37") (pin "2") (pinfunction "2_2") (pintype "passive"))
      (node (ref "U6") (pin "8") (pinfunction "SCL_8") (pintype "output"))
    )
    (net (code "34") (name "/I2C2_SCL_B") (class "Default")
      (node (ref "J10") (pin "14") (pinfunction "14_14") (pintype "passive"))
      (node (ref "R37") (pin "1") (pinfunction "1_1") (pintype "passive"))
      (node (ref "TP10") (pin "1") (pinfunction "TPt_1") (pintype "passive"))
    )
    (net (code "35") (name "/I2C2_SDA") (class "Default")
      (node (ref "R19") (pin "1") (pinfunction "1_1") (pintype "passive"))
      (node (ref "R36") (pin "2") (pinfunction "2_2") (pintype "passive"))
      (node (ref "U6") (pin "7") (pinfunction "SDA_7") (pintype "bidirectional"))
    )
    (net (code "36") (name "/I2C2_SDA_B") (class "Default")
      (node (ref "J10") (pin "12") (pinfunction "12_12") (pintype "passive"))
      (node (ref "R36") (pin "1") (pinfunction "1_1") (pintype "passive"))
      (node (ref "TP8") (pin "1") (pinfunction "TPt_1") (pintype "passive"))
    )
    (net (code "37") (name "/I2C3_SCL") (class "Default")
      (node (ref "J10") (pin "13") (pinfunction "13_13") (pintype "passive"))
      (node (ref "R20") (pin "1") (pinfunction "1_1") (pintype "passive"))
      (node (ref "TP4") (pin "1") (pinfunction "TPt_1") (pintype "passive"))
      (node (ref "U3") (pin "67") (pinfunction "PA8_67") (pintype "bidirectional"))
    )
    (net (code "38") (name "/I2C3_SDA") (class "Default")
      (node (ref "J10") (pin "15") (pinfunction "15_15") (pintype "passive"))
      (node (ref "R21") (pin "1") (pinfunction "1_1") (pintype "passive"))
      (node (ref "TP6") (pin "1") (pinfunction "TPt_1") (pintype "passive"))
      (node (ref "U3") (pin "66") (pinfunction "PC9_66") (pintype "bidirectional"))
    )
    (net (code "39") (name "/I2C_EXT_~{RESE}T") (class "Default")
      (node (ref "TP18") (pin "1") (pinfunction "TPt_1") (pintype "passive"))
      (node (ref "U3") (pin "8") (pinfunction "PC14-OSC32_IN(PC14)_8") (pintype "bidirectional"))
      (node (ref "U6") (pin "3") (pinfunction "~{RESET}_3") (pintype "input"))
    )
    (net (code "40") (name "/LED0") (class "Default")
      (node (ref "D1") (pin "1") (pinfunction "A_1") (pintype "passive"))
      (node (ref "U3") (pin "2") (pinfunction "PE3_2") (pintype "bidirectional"))
    )
    (net (code "41") (name "/LED1") (class "Default")
      (node (ref "D2") (pin "1") (pinfunction "A_1") (pintype "passive"))
      (node (ref "U3") (pin "3") (pinfunction "PE4_3") (pintype "bidirectional"))
    )
    (net (code "42") (name "/MCU_NRST") (class "Default")
      (node (ref "C35") (pin "2") (pinfunction "2_2") (pintype "passive"))
      (node (ref "J8") (pin "10") (pinfunction "10_10") (pintype "passive"))
      (node (ref "S2") (pin "1") (pinfunction "1_1") (pintype "power_in"))
      (node (ref "U3") (pin "14") (pinfunction "NRST_14") (pintype "bidirectional"))
    )
    (net (code "43") (name "/OSC_IN") (class "Default")
      (node (ref "C39") (pin "1") (pinfunction "1_1") (pintype "passive"))
      (node (ref "U3") (pin "12") (pinfunction "PH0-OSC_IN(PH0)_12") (pintype "bidirectional"))
      (node (ref "X1") (pin "3") (pinfunction "3_3") (pintype "passive"))
    )
    (net (code "44") (name "/OSC_OUT") (class "Default")
      (node (ref "C40") (pin "1") (pinfunction "1_1") (pintype "passive"))
      (node (ref "U3") (pin "13") (pinfunction "PH1-OSC_OUT(PH1)_13") (pintype "bidirectional"))
      (node (ref "X1") (pin "1") (pinfunction "1_1") (pintype "passive"))
    )
    (net (code "45") (name "/PFB") (class "Default")
      (node (ref "C3") (pin "1") (pinfunction "1_1") (pintype "passive"))
      (node (ref "C4") (pin "2") (pinfunction "2_2") (pintype "passive"))
      (node (ref "C6") (pin "2") (pinfunction "2_2") (pintype "passive"))
      (node (ref "U2") (pin "18") (pinfunction "PFBIN1_18") (pintype "input"))
      (node (ref "U2") (pin "23") (pinfunction "PFBOUT_23") (pintype "output"))
      (node (ref "U2") (pin "37") (pinfunction "PFBIN2_37") (pintype "input"))
    )
    (net (code "46") (name "/PHY_RESET") (class "Default")
      (node (ref "U2") (pin "29") (pinfunction "RESETN_29") (pintype "input"))
      (node (ref "U3") (pin "53") (pinfunction "PB14_53") (pintype "bidirectional"))
    )
    (net (code "47") (name "/PHY_RX_n") (class "Default")
      (node (ref "R23") (pin "1") (pinfunction "1_1") (pintype "passive"))
      (node (ref "U2") (pin "13") (pinfunction "RD-_13") (pintype "bidirectional"))
      (node (ref "U7") (pin "8") (pinfunction "D2-_8") (pintype "passive"))
    )
    (net (code "48") (name "/PHY_RX_p") (class "Default")
      (node (ref "R22") (pin "2") (pinfunction "2_2") (pintype "passive"))
      (node (ref "U2") (pin "14") (pinfunction "RD+_14") (pintype "bidirectional"))
      (node (ref "U7") (pin "7") (pinfunction "D2+_7") (pintype "passive"))
    )
    (net (code "49") (name "/PHY_TX_n") (class "Default")
      (node (ref "R3") (pin "1") (pinfunction "1_1") (pintype "passive"))
      (node (ref "U2") (pin "16") (pinfunction "TD-_16") (pintype "bidirectional"))
      (node (ref "U7") (pin "2") (pinfunction "D1-_2") (pintype "passive"))
    )
    (net (code "50") (name "/PHY_TX_p") (class "Default")
      (node (ref "R2") (pin "1") (pinfunction "1_1") (pintype "passive"))
      (node (ref "U2") (pin "17") (pinfunction "TD+_17") (pintype "bidirectional"))
      (node (ref "U7") (pin "1") (pinfunction "D1+_1") (pintype "passive"))
    )
    (net (code "51") (name "/SPI1_MISO") (class "Default")
      (node (ref "R34") (pin "2") (pinfunction "2_2") (pintype "passive"))
      (node (ref "U6") (pin "5") (pinfunction "MISO_5") (pintype "output"))
    )
    (net (code "52") (name "/SPI1_MISO_B") (class "Default")
      (node (ref "R34") (pin "1") (pinfunction "1_1") (pintype "passive"))
      (node (ref "TP16") (pin "1") (pinfunction "TPt_1") (pintype "passive"))
      (node (ref "U3") (pin "31") (pinfunction "PA6_31") (pintype "bidirectional"))
    )
    (net (code "53") (name "/SPI1_MOSI") (class "Default")
      (node (ref "R35") (pin "2") (pinfunction "2_2") (pintype "passive"))
      (node (ref "U6") (pin "6") (pinfunction "MOSI_6") (pintype "input"))
    )
    (net (code "54") (name "/SPI1_MOSI_B") (class "Default")
      (node (ref "R35") (pin "1") (pinfunction "1_1") (pintype "passive"))
      (node (ref "TP17") (pin "1") (pinfunction "TPt_1") (pintype "passive"))
      (node (ref "U3") (pin "91") (pinfunction "PB5_91") (pintype "bidirectional"))
    )
    (net (code "55") (name "/SPI1_NSS") (class "Default")
      (node (ref "R32") (pin "1") (pinfunction "1_1") (pintype "passive"))
      (node (ref "R33") (pin "2") (pinfunction "2_2") (pintype "passive"))
      (node (ref "U6") (pin "2") (pinfunction "~{CS}_2") (pintype "input"))
    )
    (net (code "56") (name "/SPI1_NSS_B") (class "Default")
      (node (ref "R33") (pin "1") (pinfunction "1_1") (pintype "passive"))
      (node (ref "TP14") (pin "1") (pinfunction "TPt_1") (pintype "passive"))
      (node (ref "U3") (pin "29") (pinfunction "PA4_29") (pintype "bidirectional"))
    )
    (net (code "57") (name "/SPI1_SCLK") (class "Default")
      (node (ref "R38") (pin "2") (pinfunction "2_2") (pintype "passive"))
      (node (ref "U6") (pin "11") (pinfunction "SCLK_11") (pintype "input"))
    )
    (net (code "58") (name "/SPI1_SCLK_B") (class "Default")
      (node (ref "R38") (pin "1") (pinfunction "1_1") (pintype "passive"))
      (node (ref "TP15") (pin "1") (pinfunction "TPt_1") (pintype "passive"))
      (node (ref "U3") (pin "30") (pinfunction "PA5_30") (pintype "bidirectional"))
    )
    (net (code "59") (name "/SPI4_MISO") (class "Default")
      (node (ref "J10") (pin "21") (pinfunction "21_21") (pintype "passive"))
      (node (ref "U3") (pin "44") (pinfunction "PE13_44") (pintype "bidirectional"))
    )
    (net (code "60") (name "/SPI4_MOSI") (class "Default")
      (node (ref "J10") (pin "19") (pinfunction "19_19") (pintype "passive"))
      (node (ref "U3") (pin "45") (pinfunction "PE14_45") (pintype "bidirectional"))
    )
    (net (code "61") (name "/SPI4_NSS") (class "Default")
      (node (ref "J10") (pin "22") (pinfunction "22_22") (pintype "passive"))
      (node (ref "U3") (pin "42") (pinfunction "PE11_42") (pintype "bidirectional"))
    )
    (net (code "62") (name "/SPI4_SCLK") (class "Default")
      (node (ref "J10") (pin "24") (pinfunction "24_24") (pintype "passive"))
      (node (ref "U3") (pin "43") (pinfunction "PE12_43") (pintype "bidirectional"))
    )
    (net (code "63") (name "/TCLK") (class "Default")
      (node (ref "J8") (pin "4") (pinfunction "4_4") (pintype "passive"))
      (node (ref "U3") (pin "76") (pinfunction "PA14(JTCK-SWCLK)_76") (pintype "bidirectional"))
    )
    (net (code "64") (name "/TDI") (class "Default")
      (node (ref "J8") (pin "8") (pinfunction "8_8") (pintype "passive"))
      (node (ref "U3") (pin "77") (pinfunction "PA15(JTDI)_77") (pintype "bidirectional"))
    )
    (net (code "65") (name "/TDO") (class "Default")
      (node (ref "J8") (pin "6") (pinfunction "6_6") (pintype "passive"))
      (node (ref "U3") (pin "89") (pinfunction "PB3(JTDO/TRACESWO)_89") (pintype "bidirectional"))
    )
    (net (code "66") (name "/TMS") (class "Default")
      (node (ref "J8") (pin "2") (pinfunction "2_2") (pintype "passive"))
      (node (ref "U3") (pin "72") (pinfunction "PA13(JTMS-SWDIO)_72") (pintype "bidirectional"))
    )
    (net (code "67") (name "/TempAlert") (class "Default")
      (node (ref "R15") (pin "1") (pinfunction "1_1") (pintype "passive"))
      (node (ref "U3") (pin "38") (pinfunction "PE7_38") (pintype "bidirectional"))
      (node (ref "U8") (pin "3") (pinfunction "Alert_3") (pintype "passive"))
    )
    (net (code "68") (name "/UART3_DATA_A") (class "Default")
      (node (ref "U3") (pin "55") (pinfunction "PD8_55") (pintype "bidirectional"))
      (node (ref "U3") (pin "56") (pinfunction "PD9_56") (pintype "bidirectional"))
      (node (ref "U5") (pin "2") (pinfunction "A1_2") (pintype "power_in"))
    )
    (net (code "69") (name "/UART3_DATA_B") (class "Default")
      (node (ref "J10") (pin "2") (pinfunction "2_2") (pintype "passive"))
      (node (ref "TP1") (pin "1") (pinfunction "TPt_1") (pintype "passive"))
      (node (ref "U5") (pin "13") (pinfunction "B1_13") (pintype "power_in"))
    )
    (net (code "70") (name "/UART4_DATA_A") (class "Default")
      (node (ref "U3") (pin "78") (pinfunction "PC10_78") (pintype "bidirectional"))
      (node (ref "U3") (pin "79") (pinfunction "PC11_79") (pintype "bidirectional"))
      (node (ref "U5") (pin "3") (pinfunction "A2_3") (pintype "power_in"))
    )
    (net (code "71") (name "/UART4_DATA_B") (class "Default")
      (node (ref "J10") (pin "6") (pinfunction "6_6") (pintype "passive"))
      (node (ref "TP2") (pin "1") (pinfunction "TPt_1") (pintype "passive"))
      (node (ref "U5") (pin "12") (pinfunction "B2_12") (pintype "power_in"))
    )
    (net (code "72") (name "/UART5_DATA_A") (class "Default")
      (node (ref "U3") (pin "80") (pinfunction "PC12_80") (pintype "bidirectional"))
      (node (ref "U3") (pin "83") (pinfunction "PD2_83") (pintype "bidirectional"))
      (node (ref "U5") (pin "4") (pinfunction "A3_4") (pintype "power_in"))
    )
    (net (code "73") (name "/UART5_DATA_B") (class "Default")
      (node (ref "J10") (pin "8") (pinfunction "8_8") (pintype "passive"))
      (node (ref "TP3") (pin "1") (pinfunction "TPt_1") (pintype "passive"))
      (node (ref "U5") (pin "11") (pinfunction "B3_11") (pintype "power_in"))
    )
    (net (code "74") (name "/UART6_DATA_A") (class "Default")
      (node (ref "U3") (pin "63") (pinfunction "PC6_63") (pintype "bidirectional"))
      (node (ref "U3") (pin "64") (pinfunction "PC7_64") (pintype "bidirectional"))
      (node (ref "U5") (pin "5") (pinfunction "A4_5") (pintype "power_in"))
    )
    (net (code "75") (name "/UART6_DATA_B") (class "Default")
      (node (ref "J10") (pin "10") (pinfunction "10_10") (pintype "passive"))
      (node (ref "TP5") (pin "1") (pinfunction "TPt_1") (pintype "passive"))
      (node (ref "U5") (pin "10") (pinfunction "B4_10") (pintype "power_in"))
    )
    (net (code "76") (name "/USB_DM") (class "Default")
      (node (ref "J5") (pin "2") (pinfunction "2_2") (pintype "passive"))
      (node (ref "U3") (pin "70") (pinfunction "PA11_70") (pintype "bidirectional"))
    )
    (net (code "77") (name "/USB_DP") (class "Default")
      (node (ref "J5") (pin "3") (pinfunction "3_3") (pintype "passive"))
      (node (ref "U3") (pin "71") (pinfunction "PA12_71") (pintype "bidirectional"))
    )
    (net (code "78") (name "3V3") (class "Default")
      (node (ref "C10") (pin "2") (pinfunction "2_2") (pintype "passive"))
      (node (ref "C11") (pin "2") (pinfunction "2_2") (pintype "passive"))
      (node (ref "C12") (pin "2") (pinfunction "2_2") (pintype "passive"))
      (node (ref "C13") (pin "2") (pinfunction "2_2") (pintype "passive"))
      (node (ref "C14") (pin "2") (pinfunction "2_2") (pintype "passive"))
      (node (ref "C15") (pin "2") (pinfunction "2_2") (pintype "passive"))
      (node (ref "C16") (pin "2") (pinfunction "2_2") (pintype "passive"))
      (node (ref "C17") (pin "2") (pinfunction "2_2") (pintype "passive"))
      (node (ref "C18") (pin "2") (pinfunction "2_2") (pintype "passive"))
      (node (ref "C19") (pin "2") (pinfunction "2_2") (pintype "passive"))
      (node (ref "C20") (pin "2") (pinfunction "2_2") (pintype "passive"))
      (node (ref "C21") (pin "2") (pinfunction "2_2") (pintype "passive"))
      (node (ref "C22") (pin "2") (pinfunction "2_2") (pintype "passive"))
      (node (ref "C23") (pin "2") (pinfunction "2_2") (pintype "passive"))
      (node (ref "C24") (pin "2") (pinfunction "2_2") (pintype "passive"))
      (node (ref "C27") (pin "2") (pinfunction "2_2") (pintype "passive"))
      (node (ref "C28") (pin "2") (pinfunction "2_2") (pintype "passive"))
      (node (ref "C31") (pin "2") (pinfunction "2_2") (pintype "passive"))
      (node (ref "C33") (pin "2") (pinfunction "2_2") (pintype "passive"))
      (node (ref "C34") (pin "2") (pinfunction "2_2") (pintype "passive"))
      (node (ref "C36") (pin "2") (pinfunction "2_2") (pintype "passive"))
      (node (ref "C41") (pin "2") (pinfunction "2_2") (pintype "passive"))
      (node (ref "C43") (pin "2") (pinfunction "2_2") (pintype "passive"))
      (node (ref "C44") (pin "2") (pinfunction "2_2") (pintype "passive"))
      (node (ref "C45") (pin "2") (pinfunction "2_2") (pintype "passive"))
      (node (ref "C46") (pin "1") (pinfunction "1_1") (pintype "passive"))
      (node (ref "C48") (pin "2") (pinfunction "2_2") (pintype "passive"))
      (node (ref "C5") (pin "2") (pinfunction "2_2") (pintype "passive"))
      (node (ref "C50") (pin "1") (pinfunction "1_1") (pintype "passive"))
      (node (ref "C7") (pin "2") (pinfunction "2_2") (pintype "passive"))
      (node (ref "C8") (pin "2") (pinfunction "2_2") (pintype "passive"))
      (node (ref "C9") (pin "2") (pinfunction "2_2") (pintype "passive"))
      (node (ref "D5") (pin "1") (pinfunction "A_1") (pintype "passive"))
      (node (ref "FB1") (pin "1") (pinfunction "1_1") (pintype "passive"))
      (node (ref "J10") (pin "3") (pinfunction "3_3") (pintype "passive"))
      (node (ref "J10") (pin "5") (pinfunction "5_5") (pintype "passive"))
      (node (ref "J10") (pin "7") (pinfunction "7_7") (pintype "passive"))
      (node (ref "J10") (pin "9") (pinfunction "9_9") (pintype "passive"))
      (node (ref "J8") (pin "1") (pinfunction "1_1") (pintype "passive"))
      (node (ref "R12") (pin "2") (pinfunction "2_2") (pintype "passive"))
      (node (ref "R13") (pin "2") (pinfunction "2_2") (pintype "passive"))
      (node (ref "R15") (pin "2") (pinfunction "2_2") (pintype "passive"))
      (node (ref "R16") (pin "2") (pinfunction "2_2") (pintype "passive"))
      (node (ref "R17") (pin "2") (pinfunction "2_2") (pintype "passive"))
      (node (ref "R18") (pin "2") (pinfunction "2_2") (pintype "passive"))
      (node (ref "R19") (pin "2") (pinfunction "2_2") (pintype "passive"))
      (node (ref "R2") (pin "2") (pinfunction "2_2") (pintype "passive"))
      (node (ref "R20") (pin "2") (pinfunction "2_2") (pintype "passive"))
      (node (ref "R21") (pin "2") (pinfunction "2_2") (pintype "passive"))
      (node (ref "R22") (pin "1") (pinfunction "1_1") (pintype "passive"))
      (node (ref "R23") (pin "2") (pinfunction "2_2") (pintype "passive"))
      (node (ref "R26") (pin "2") (pinfunction "2_2") (pintype "passive"))
      (node (ref "R27") (pin "2") (pinfunction "2_2") (pintype "passive"))
      (node (ref "R28") (pin "2") (pinfunction "2_2") (pintype "passive"))
      (node (ref "R3") (pin "2") (pinfunction "2_2") (pintype "passive"))
      (node (ref "R8") (pin "1") (pinfunction "1_1") (pintype "passive"))
      (node (ref "S1") (pin "1") (pinfunction "1_1") (pintype "power_in"))
      (node (ref "U1") (pin "8") (pinfunction "Vcc_8") (pintype "power_in"))
      (node (ref "U2") (pin "22") (pinfunction "AVDD33_22") (pintype "power_in"))
      (node (ref "U2") (pin "32") (pinfunction "VDD33_IO_32") (pintype "power_in"))
      (node (ref "U2") (pin "48") (pinfunction "VDD33_IO_48") (pintype "power_in"))
      (node (ref "U3") (pin "100") (pinfunction "VDD_100") (pintype "power_in"))
      (node (ref "U3") (pin "11") (pinfunction "VDD_11") (pintype "power_in"))
      (node (ref "U3") (pin "19") (pinfunction "VDD_19") (pintype "power_in"))
      (node (ref "U3") (pin "28") (pinfunction "VDD_28") (pintype "power_in"))
      (node (ref "U3") (pin "50") (pinfunction "VDD_50") (pintype "power_in"))
      (node (ref "U3") (pin "6") (pinfunction "VBAT_6") (pintype "power_in"))
      (node (ref "U3") (pin "75") (pinfunction "VDD_75") (pintype "power_in"))
      (node (ref "U4") (pin "1") (pinfunction "ST_1") (pintype "passive"))
      (node (ref "U4") (pin "4") (pinfunction "VCC_4") (pintype "passive"))
      (node (ref "U5") (pin "1") (pinfunction "VCCA_1") (pintype "power_in"))
      (node (ref "U6") (pin "12") (pinfunction "VDD_12") (pintype "input"))
      (node (ref "U7") (pin "3") (pinfunction "TD1_3") (pintype "passive"))
      (node (ref "U7") (pin "6") (pinfunction "TD2_6") (pintype "passive"))
      (node (ref "U8") (pin "8") (pinfunction "Vdd_8") (pintype "passive"))
    )
    (net (code "79") (name "3V3_ANA") (class "Default")
      (node (ref "C25") (pin "2") (pinfunction "2_2") (pintype "passive"))
      (node (ref "C26") (pin "2") (pinfunction "2_2") (pintype "passive"))
      (node (ref "FB1") (pin "2") (pinfunction "2_2") (pintype "passive"))
      (node (ref "R1") (pin "2") (pinfunction "2_2") (pintype "passive"))
      (node (ref "U3") (pin "22") (pinfunction "VDDA_22") (pintype "power_in"))
    )
    (net (code "80") (name "5V") (class "Default")
      (node (ref "C47") (pin "2") (pinfunction "2_2") (pintype "passive"))
      (node (ref "C49") (pin "1") (pinfunction "1_1") (pintype "passive"))
      (node (ref "J10") (pin "1") (pinfunction "1_1") (pintype "passive"))
      (node (ref "U5") (pin "14") (pinfunction "VCCB_14") (pintype "power_in"))
    )
    (net (code "81") (name "GND") (class "Default")
      (node (ref "C1") (pin "1") (pinfunction "1_1") (pintype "passive"))
      (node (ref "C10") (pin "1") (pinfunction "1_1") (pintype "passive"))
      (node (ref "C11") (pin "1") (pinfunction "1_1") (pintype "passive"))
      (node (ref "C12") (pin "1") (pinfunction "1_1") (pintype "passive"))
      (node (ref "C13") (pin "1") (pinfunction "1_1") (pintype "passive"))
      (node (ref "C14") (pin "1") (pinfunction "1_1") (pintype "passive"))
      (node (ref "C15") (pin "1") (pinfunction "1_1") (pintype "passive"))
      (node (ref "C16") (pin "1") (pinfunction "1_1") (pintype "passive"))
      (node (ref "C17") (pin "1") (pinfunction "1_1") (pintype "passive"))
      (node (ref "C18") (pin "1") (pinfunction "1_1") (pintype "passive"))
      (node (ref "C19") (pin "1") (pinfunction "1_1") (pintype "passive"))
      (node (ref "C2") (pin "1") (pinfunction "1_1") (pintype "passive"))
      (node (ref "C20") (pin "1") (pinfunction "1_1") (pintype "passive"))
      (node (ref "C21") (pin "1") (pinfunction "1_1") (pintype "passive"))
      (node (ref "C22") (pin "1") (pinfunction "1_1") (pintype "passive"))
      (node (ref "C23") (pin "1") (pinfunction "1_1") (pintype "passive"))
      (node (ref "C24") (pin "1") (pinfunction "1_1") (pintype "passive"))
      (node (ref "C25") (pin "1") (pinfunction "1_1") (pintype "passive"))
      (node (ref "C26") (pin "1") (pinfunction "1_1") (pintype "passive"))
      (node (ref "C27") (pin "1") (pinfunction "1_1") (pintype "passive"))
      (node (ref "C28") (pin "1") (pinfunction "1_1") (pintype "passive"))
      (node (ref "C29") (pin "1") (pinfunction "1_1") (pintype "passive"))
      (node (ref "C3") (pin "2") (pinfunction "2_2") (pintype "passive"))
      (node (ref "C31") (pin "1") (pinfunction "1_1") (pintype "passive"))
      (node (ref "C33") (pin "1") (pinfunction "1_1") (pintype "passive"))
      (node (ref "C34") (pin "1") (pinfunction "1_1") (pintype "passive"))
      (node (ref "C35") (pin "1") (pinfunction "1_1") (pintype "passive"))
      (node (ref "C36") (pin "1") (pinfunction "1_1") (pintype "passive"))
      (node (ref "C37") (pin "1") (pinfunction "1_1") (pintype "passive"))
      (node (ref "C38") (pin "1") (pinfunction "1_1") (pintype "passive"))
      (node (ref "C39") (pin "2") (pinfunction "2_2") (pintype "passive"))
      (node (ref "C4") (pin "1") (pinfunction "1_1") (pintype "passive"))
      (node (ref "C40") (pin "2") (pinfunction "2_2") (pintype "passive"))
      (node (ref "C41") (pin "1") (pinfunction "1_1") (pintype "passive"))
      (node (ref "C42") (pin "1") (pinfunction "1_1") (pintype "passive"))
      (node (ref "C43") (pin "1") (pinfunction "1_1") (pintype "passive"))
      (node (ref "C44") (pin "1") (pinfunction "1_1") (pintype "passive"))
      (node (ref "C45") (pin "1") (pinfunction "1_1") (pintype "passive"))
      (node (ref "C46") (pin "2") (pinfunction "2_2") (pintype "passive"))
      (node (ref "C47") (pin "1") (pinfunction "1_1") (pintype "passive"))
      (node (ref "C48") (pin "1") (pinfunction "1_1") (pintype "passive"))
      (node (ref "C49") (pin "2") (pinfunction "2_2") (pintype "passive"))
      (node (ref "C5") (pin "1") (pinfunction "1_1") (pintype "passive"))
      (node (ref "C50") (pin "2") (pinfunction "2_2") (pintype "passive"))
      (node (ref "C6") (pin "1") (pinfunction "1_1") (pintype "passive"))
      (node (ref "C7") (pin "1") (pinfunction "1_1") (pintype "passive"))
      (node (ref "C8") (pin "1") (pinfunction "1_1") (pintype "passive"))
      (node (ref "C9") (pin "1") (pinfunction "1_1") (pintype "passive"))
      (node (ref "D5") (pin "2") (pinfunction "C_2") (pintype "passive"))
      (node (ref "J10") (pin "11") (pinfunction "11_11") (pintype "passive"))
      (node (ref "J10") (pin "17") (pinfunction "17_17") (pintype "passive"))
      (node (ref "J10") (pin "20") (pinfunction "20_20") (pintype "passive"))
      (node (ref "J10") (pin "23") (pinfunction "23_23") (pintype "passive"))
      (node (ref "J10") (pin "25") (pinfunction "25_25") (pintype "passive"))
      (node (ref "J10") (pin "26") (pinfunction "26_26") (pintype "passive"))
      (node (ref "J10") (pin "28") (pinfunction "28_28") (pintype "passive"))
      (node (ref "J10") (pin "30") (pinfunction "30_30") (pintype "passive"))
      (node (ref "J10") (pin "31") (pinfunction "31_31") (pintype "passive"))
      (node (ref "J10") (pin "33") (pinfunction "33_33") (pintype "passive"))
      (node (ref "J10") (pin "35") (pinfunction "35_35") (pintype "passive"))
      (node (ref "J10") (pin "36") (pinfunction "36_36") (pintype "passive"))
      (node (ref "J10") (pin "4") (pinfunction "4_4") (pintype "passive"))
      (node (ref "J5") (pin "5") (pinfunction "5_5") (pintype "passive"))
      (node (ref "J8") (pin "3") (pinfunction "3_3") (pintype "passive"))
      (node (ref "J8") (pin "5") (pinfunction "5_5") (pintype "passive"))
      (node (ref "J8") (pin "9") (pinfunction "9_9") (pintype "passive"))
      (node (ref "J9") (pin "2") (pinfunction "2_2") (pintype "passive"))
      (node (ref "R10") (pin "1") (pinfunction "1_1") (pintype "passive"))
      (node (ref "R11") (pin "1") (pinfunction "1_1") (pintype "passive"))
      (node (ref "R14") (pin "1") (pinfunction "1_1") (pintype "passive"))
      (node (ref "R29") (pin "1") (pinfunction "1_1") (pintype "passive"))
      (node (ref "R30") (pin "1") (pinfunction "1_1") (pintype "passive"))
      (node (ref "R31") (pin "1") (pinfunction "1_1") (pintype "passive"))
      (node (ref "R32") (pin "2") (pinfunction "2_2") (pintype "passive"))
      (node (ref "R4") (pin "1") (pinfunction "1_1") (pintype "passive"))
      (node (ref "R5") (pin "1") (pinfunction "1_1") (pintype "passive"))
      (node (ref "R6") (pin "1") (pinfunction "1_1") (pintype "passive"))
      (node (ref "R7") (pin "1") (pinfunction "1_1") (pintype "passive"))
      (node (ref "R9") (pin "1") (pinfunction "1_1") (pintype "passive"))
      (node (ref "S2") (pin "2") (pinfunction "2_2") (pintype "power_in"))
      (node (ref "TP13") (pin "1") (pinfunction "TPt_1") (pintype "passive"))
      (node (ref "U1") (pin "3") (pinfunction "A2_3") (pintype "passive"))
      (node (ref "U1") (pin "4") (pinfunction "Vss_4") (pintype "power_in"))
      (node (ref "U1") (pin "7") (pinfunction "WP_7") (pintype "passive"))
      (node (ref "U2") (pin "15") (pinfunction "AGND_15") (pintype "power_in"))
      (node (ref "U2") (pin "19") (pinfunction "AGND_19") (pintype "power_in"))
      (node (ref "U2") (pin "35") (pinfunction "IOGND_35") (pintype "power_in"))
      (node (ref "U2") (pin "36") (pinfunction "DGND_36") (pintype "power_in"))
      (node (ref "U2") (pin "47") (pinfunction "IOGND_47") (pintype "power_in"))
      (node (ref "U3") (pin "10") (pinfunction "VSS_10") (pintype "power_in"))
      (node (ref "U3") (pin "20") (pinfunction "VSSA_20") (pintype "power_in"))
      (node (ref "U3") (pin "27") (pinfunction "VSS_27") (pintype "power_in"))
      (node (ref "U3") (pin "37") (pinfunction "PB2-BOOT1(PB2)_37") (pintype "bidirectional"))
      (node (ref "U3") (pin "74") (pinfunction "VSS_74") (pintype "power_in"))
      (node (ref "U3") (pin "99") (pinfunction "VSS_99") (pintype "power_in"))
      (node (ref "U4") (pin "2") (pinfunction "GND_2") (pintype "passive"))
      (node (ref "U5") (pin "7") (pinfunction "GND_7") (pintype "power_in"))
      (node (ref "U6") (pin "4") (pinfunction "VSS_4") (pintype "input"))
      (node (ref "U8") (pin "4") (pinfunction "GND_4") (pintype "passive"))
      (node (ref "U8") (pin "5") (pinfunction "A2_5") (pintype "passive"))
      (node (ref "U8") (pin "6") (pinfunction "A1_6") (pintype "passive"))
      (node (ref "U8") (pin "9") (pinfunction "GND_9") (pintype "passive"))
      (node (ref "X1") (pin "2") (pinfunction "GND_2") (pintype "passive"))
      (node (ref "X1") (pin "4") (pinfunction "GND_4") (pintype "passive"))
    )
    (net (code "82") (name "Net-(D1-K)") (class "Default")
      (node (ref "D1") (pin "2") (pinfunction "K_2") (pintype "passive"))
      (node (ref "R4") (pin "2") (pinfunction "2_2") (pintype "passive"))
    )
    (net (code "83") (name "Net-(D2-K)") (class "Default")
      (node (ref "D2") (pin "2") (pinfunction "K_2") (pintype "passive"))
      (node (ref "R6") (pin "2") (pinfunction "2_2") (pintype "passive"))
    )
    (net (code "84") (name "Net-(D3-K)") (class "Default")
      (node (ref "D3") (pin "2") (pinfunction "K_2") (pintype "passive"))
      (node (ref "R7") (pin "2") (pinfunction "2_2") (pintype "passive"))
    )
    (net (code "85") (name "Net-(D4-K)") (class "Default")
      (node (ref "D4") (pin "2") (pinfunction "K_2") (pintype "passive"))
      (node (ref "R5") (pin "2") (pinfunction "2_2") (pintype "passive"))
    )
    (net (code "86") (name "Net-(U1-A1)") (class "Default")
      (node (ref "R27") (pin "1") (pinfunction "1_1") (pintype "passive"))
      (node (ref "R30") (pin "2") (pinfunction "2_2") (pintype "passive"))
      (node (ref "U1") (pin "2") (pinfunction "A1_2") (pintype "passive"))
    )
    (net (code "87") (name "Net-(U2A-RBIAS)") (class "Default")
      (node (ref "R10") (pin "2") (pinfunction "2_2") (pintype "passive"))
      (node (ref "U2") (pin "24") (pinfunction "RBIAS_24") (pintype "passive"))
    )
    (net (code "88") (name "Net-(U2A-RESERVED)") (class "Default")
      (node (ref "R26") (pin "1") (pinfunction "1_1") (pintype "passive"))
      (node (ref "U2") (pin "20") (pinfunction "RESERVED_20") (pintype "passive"))
    )
    (net (code "89") (name "Net-(U2A-RX_DV)") (class "Default")
      (node (ref "R13") (pin "1") (pinfunction "1_1") (pintype "passive"))
      (node (ref "U2") (pin "39") (pinfunction "RX_DV_39") (pintype "tri_state"))
    )
    (net (code "90") (name "Net-(U2A-SW_STRAPN)") (class "Default")
      (node (ref "R9") (pin "2") (pinfunction "2_2") (pintype "passive"))
      (node (ref "U2") (pin "21") (pinfunction "SW_STRAPN_21") (pintype "input"))
    )
    (net (code "91") (name "Net-(U3A-VCAP_1)") (class "Default")
      (node (ref "C38") (pin "2") (pinfunction "2_2") (pintype "passive"))
      (node (ref "U3") (pin "49") (pinfunction "VCAP_1_49") (pintype "power_in"))
    )
    (net (code "92") (name "Net-(U3A-VCAP_2)") (class "Default")
      (node (ref "C37") (pin "2") (pinfunction "2_2") (pintype "passive"))
      (node (ref "U3") (pin "73") (pinfunction "VCAP_2_73") (pintype "power_in"))
    )
    (net (code "93") (name "Net-(U3B-VREF+)") (class "Default")
      (node (ref "C1") (pin "2") (pinfunction "2_2") (pintype "passive"))
      (node (ref "C2") (pin "2") (pinfunction "2_2") (pintype "passive"))
      (node (ref "R1") (pin "1") (pinfunction "1_1") (pintype "passive"))
      (node (ref "U3") (pin "21") (pinfunction "VREF+_21") (pintype "power_in"))
    )
    (net (code "94") (name "Net-(U6-~{WAKEUP}{slash}IO4)") (class "Default")
      (node (ref "R31") (pin "2") (pinfunction "2_2") (pintype "passive"))
      (node (ref "U6") (pin "15") (pinfunction "~{WAKEUP}/IO4_15") (pintype "bidirectional"))
    )
    (net (code "95") (name "Net-(U8-A0)") (class "Default")
      (node (ref "R28") (pin "1") (pinfunction "1_1") (pintype "passive"))
      (node (ref "R29") (pin "2") (pinfunction "2_2") (pintype "passive"))
      (node (ref "U8") (pin "7") (pinfunction "A0_7") (pintype "passive"))
    )
    (net (code "96") (name "unconnected-(J5-Pad1)") (class "Default")
      (node (ref "J5") (pin "1") (pinfunction "1_1") (pintype "passive"))
    )
    (net (code "97") (name "unconnected-(J5-Pad4)") (class "Default")
      (node (ref "J5") (pin "4") (pinfunction "4_4") (pintype "passive"))
    )
    (net (code "98") (name "unconnected-(J8-Pad7)") (class "Default")
      (node (ref "J8") (pin "7") (pinfunction "7_7") (pintype "passive"))
    )
    (net (code "99") (name "unconnected-(U1-NC-Pad1)") (class "Default")
      (node (ref "U1") (pin "1") (pinfunction "NC_1") (pintype "passive"))
    )
    (net (code "100") (name "unconnected-(U2A-CLKOUT-Pad25)") (class "Default")
      (node (ref "U2") (pin "25") (pinfunction "CLKOUT_25") (pintype "tri_state"))
    )
    (net (code "101") (name "unconnected-(U2A-COL{slash}PHYAD0-Pad42)") (class "Default")
      (node (ref "U2") (pin "42") (pinfunction "COL/PHYAD0_42") (pintype "tri_state"))
    )
    (net (code "102") (name "unconnected-(U2A-JTAG_TCK-Pad8)") (class "Default")
      (node (ref "U2") (pin "8") (pinfunction "JTAG_TCK_8") (pintype "input"))
    )
    (net (code "103") (name "unconnected-(U2A-JTAG_TDI-Pad12)") (class "Default")
      (node (ref "U2") (pin "12") (pinfunction "JTAG_TDI_12") (pintype "input"))
    )
    (net (code "104") (name "unconnected-(U2A-JTAG_TDO-Pad9)") (class "Default")
      (node (ref "U2") (pin "9") (pinfunction "JTAG_TDO_9") (pintype "output"))
    )
    (net (code "105") (name "unconnected-(U2A-JTAG_TMS-Pad10)") (class "Default")
      (node (ref "U2") (pin "10") (pinfunction "JTAG_TMS_10") (pintype "input"))
    )
    (net (code "106") (name "unconnected-(U2A-JTAG_TRSTN-Pad11)") (class "Default")
      (node (ref "U2") (pin "11") (pinfunction "JTAG_TRSTN_11") (pintype "input"))
    )
    (net (code "107") (name "unconnected-(U2A-LED_ACT{slash}COL{slash}AN_EN-Pad26)") (class "Default")
      (node (ref "U2") (pin "26") (pinfunction "LED_ACT/COL/AN_EN_26") (pintype "tri_state"))
    )
    (net (code "108") (name "unconnected-(U2A-LED_LINK{slash}AN0-Pad28)") (class "Default")
      (node (ref "U2") (pin "28") (pinfunction "LED_LINK/AN0_28") (pintype "tri_state"))
    )
    (net (code "109") (name "unconnected-(U2A-LED_SPEED{slash}AN1-Pad27)") (class "Default")
      (node (ref "U2") (pin "27") (pinfunction "LED_SPEED/AN1_27") (pintype "tri_state"))
    )
    (net (code "110") (name "unconnected-(U2A-PWR_DWN{slash}INTN-Pad7)") (class "Default")
      (node (ref "U2") (pin "7") (pinfunction "PWR_DWN/INTN_7") (pintype "bidirectional"))
    )
    (net (code "111") (name "unconnected-(U2A-RXD_2{slash}PHYAD3-Pad45)") (class "Default")
      (node (ref "U2") (pin "45") (pinfunction "RXD_2/PHYAD3_45") (pintype "tri_state"))
    )
    (net (code "112") (name "unconnected-(U2A-RXD_3{slash}PHYAD4-Pad46)") (class "Default")
      (node (ref "U2") (pin "46") (pinfunction "RXD_3/PHYAD4_46") (pintype "tri_state"))
    )
    (net (code "113") (name "unconnected-(U2A-RX_CLK-Pad38)") (class "Default")
      (node (ref "U2") (pin "38") (pinfunction "RX_CLK_38") (pintype "tri_state"))
    )
    (net (code "114") (name "unconnected-(U2A-RX_ER{slash}MDIX_EN-Pad41)") (class "Default")
      (node (ref "U2") (pin "41") (pinfunction "RX_ER/MDIX_EN_41") (pintype "tri_state"))
    )
    (net (code "115") (name "unconnected-(U2A-TXD_2-Pad5)") (class "Default")
      (node (ref "U2") (pin "5") (pinfunction "TXD_2_5") (pintype "input"))
    )
    (net (code "116") (name "unconnected-(U2A-TXD_3-Pad6)") (class "Default")
      (node (ref "U2") (pin "6") (pinfunction "TXD_3_6") (pintype "input"))
    )
    (net (code "117") (name "unconnected-(U2A-TX_CLK-Pad1)") (class "Default")
      (node (ref "U2") (pin "1") (pinfunction "TX_CLK_1") (pintype "tri_state"))
    )
    (net (code "118") (name "unconnected-(U2A-XO-Pad33)") (class "Default")
      (node (ref "U2") (pin "33") (pinfunction "XO_33") (pintype "passive"))
    )
    (net (code "119") (name "unconnected-(U3A-PA0-WKUP(PA0)-Pad23)") (class "Default")
      (node (ref "U3") (pin "23") (pinfunction "PA0-WKUP(PA0)_23") (pintype "bidirectional"))
    )
    (net (code "120") (name "unconnected-(U3A-PA9-Pad68)") (class "Default")
      (node (ref "U3") (pin "68") (pinfunction "PA9_68") (pintype "bidirectional"))
    )
    (net (code "121") (name "unconnected-(U3A-PB4(NJTRST)-Pad90)") (class "Default")
      (node (ref "U3") (pin "90") (pinfunction "PB4(NJTRST)_90") (pintype "bidirectional"))
    )
    (net (code "122") (name "unconnected-(U3A-PB8-Pad95)") (class "Default")
      (node (ref "U3") (pin "95") (pinfunction "PB8_95") (pintype "bidirectional"))
    )
    (net (code "123") (name "unconnected-(U3A-PB9-Pad96)") (class "Default")
      (node (ref "U3") (pin "96") (pinfunction "PB9_96") (pintype "bidirectional"))
    )
    (net (code "124") (name "unconnected-(U3A-PB15-Pad54)") (class "Default")
      (node (ref "U3") (pin "54") (pinfunction "PB15_54") (pintype "bidirectional"))
    )
    (net (code "125") (name "unconnected-(U3A-PC0-Pad15)") (class "Default")
      (node (ref "U3") (pin "15") (pinfunction "PC0_15") (pintype "bidirectional"))
    )
    (net (code "126") (name "unconnected-(U3A-PC2-Pad17)") (class "Default")
      (node (ref "U3") (pin "17") (pinfunction "PC2_17") (pintype "bidirectional"))
    )
    (net (code "127") (name "unconnected-(U3A-PC3-Pad18)") (class "Default")
      (node (ref "U3") (pin "18") (pinfunction "PC3_18") (pintype "bidirectional"))
    )
    (net (code "128") (name "unconnected-(U3A-PC8-Pad65)") (class "Default")
      (node (ref "U3") (pin "65") (pinfunction "PC8_65") (pintype "bidirectional"))
    )
    (net (code "129") (name "unconnected-(U3A-PC13-Pad7)") (class "Default")
      (node (ref "U3") (pin "7") (pinfunction "PC13_7") (pintype "bidirectional"))
    )
    (net (code "130") (name "unconnected-(U3A-PD0-Pad81)") (class "Default")
      (node (ref "U3") (pin "81") (pinfunction "PD0_81") (pintype "bidirectional"))
    )
    (net (code "131") (name "unconnected-(U3A-PD1-Pad82)") (class "Default")
      (node (ref "U3") (pin "82") (pinfunction "PD1_82") (pintype "bidirectional"))
    )
    (net (code "132") (name "unconnected-(U3A-PD3-Pad84)") (class "Default")
      (node (ref "U3") (pin "84") (pinfunction "PD3_84") (pintype "bidirectional"))
    )
    (net (code "133") (name "unconnected-(U3A-PD4-Pad85)") (class "Default")
      (node (ref "U3") (pin "85") (pinfunction "PD4_85") (pintype "bidirectional"))
    )
    (net (code "134") (name "unconnected-(U3A-PD5-Pad86)") (class "Default")
      (node (ref "U3") (pin "86") (pinfunction "PD5_86") (pintype "bidirectional"))
    )
    (net (code "135") (name "unconnected-(U3A-PD6-Pad87)") (class "Default")
      (node (ref "U3") (pin "87") (pinfunction "PD6_87") (pintype "bidirectional"))
    )
    (net (code "136") (name "unconnected-(U3A-PD7-Pad88)") (class "Default")
      (node (ref "U3") (pin "88") (pinfunction "PD7_88") (pintype "bidirectional"))
    )
    (net (code "137") (name "unconnected-(U3A-PD11-Pad58)") (class "Default")
      (node (ref "U3") (pin "58") (pinfunction "PD11_58") (pintype "bidirectional"))
    )
    (net (code "138") (name "unconnected-(U3A-PD13-Pad60)") (class "Default")
      (node (ref "U3") (pin "60") (pinfunction "PD13_60") (pintype "bidirectional"))
    )
    (net (code "139") (name "unconnected-(U3A-PD14-Pad61)") (class "Default")
      (node (ref "U3") (pin "61") (pinfunction "PD14_61") (pintype "bidirectional"))
    )
    (net (code "140") (name "unconnected-(U3A-PE2-Pad1)") (class "Default")
      (node (ref "U3") (pin "1") (pinfunction "PE2_1") (pintype "bidirectional"))
    )
    (net (code "141") (name "unconnected-(U3A-PE5-Pad4)") (class "Default")
      (node (ref "U3") (pin "4") (pinfunction "PE5_4") (pintype "bidirectional"))
    )
    (net (code "142") (name "unconnected-(U3A-PE6-Pad5)") (class "Default")
      (node (ref "U3") (pin "5") (pinfunction "PE6_5") (pintype "bidirectional"))
    )
    (net (code "143") (name "unconnected-(U3A-PE8-Pad39)") (class "Default")
      (node (ref "U3") (pin "39") (pinfunction "PE8_39") (pintype "bidirectional"))
    )
    (net (code "144") (name "unconnected-(U3A-PE9-Pad40)") (class "Default")
      (node (ref "U3") (pin "40") (pinfunction "PE9_40") (pintype "bidirectional"))
    )
    (net (code "145") (name "unconnected-(U3A-PE10-Pad41)") (class "Default")
      (node (ref "U3") (pin "41") (pinfunction "PE10_41") (pintype "bidirectional"))
    )
    (net (code "146") (name "unconnected-(U5-NC-Pad6)") (class "Default")
      (node (ref "U5") (pin "6") (pinfunction "NC_6") (pintype "power_in"))
    )
    (net (code "147") (name "unconnected-(U5-NC-Pad9)") (class "Default")
      (node (ref "U5") (pin "9") (pinfunction "NC_9") (pintype "power_in"))
    )
    (net (code "148") (name "unconnected-(U6-GPIO0-Pad1)") (class "Default")
      (node (ref "U6") (pin "1") (pinfunction "GPIO0_1") (pintype "bidirectional"))
    )
    (net (code "149") (name "unconnected-(U6-GPIO1-Pad9)") (class "Default")
      (node (ref "U6") (pin "9") (pinfunction "GPIO1_9") (pintype "bidirectional"))
    )
    (net (code "150") (name "unconnected-(U6-GPIO2-Pad10)") (class "Default")
      (node (ref "U6") (pin "10") (pinfunction "GPIO2_10") (pintype "bidirectional"))
    )
    (net (code "151") (name "unconnected-(U6-GPIO3-Pad13)") (class "Default")
      (node (ref "U6") (pin "13") (pinfunction "GPIO3_13") (pintype "bidirectional"))
    )
    (net (code "152") (name "unconnected-(U6-IO5-Pad16)") (class "Default")
      (node (ref "U6") (pin "16") (pinfunction "IO5_16") (pintype "bidirectional"))
    )
  )
)
